# AJMG_2550XD_Silver_Jubilee_-_wersja_pryw.net
KiCad netlist of a schematic drawn in Altium Designer
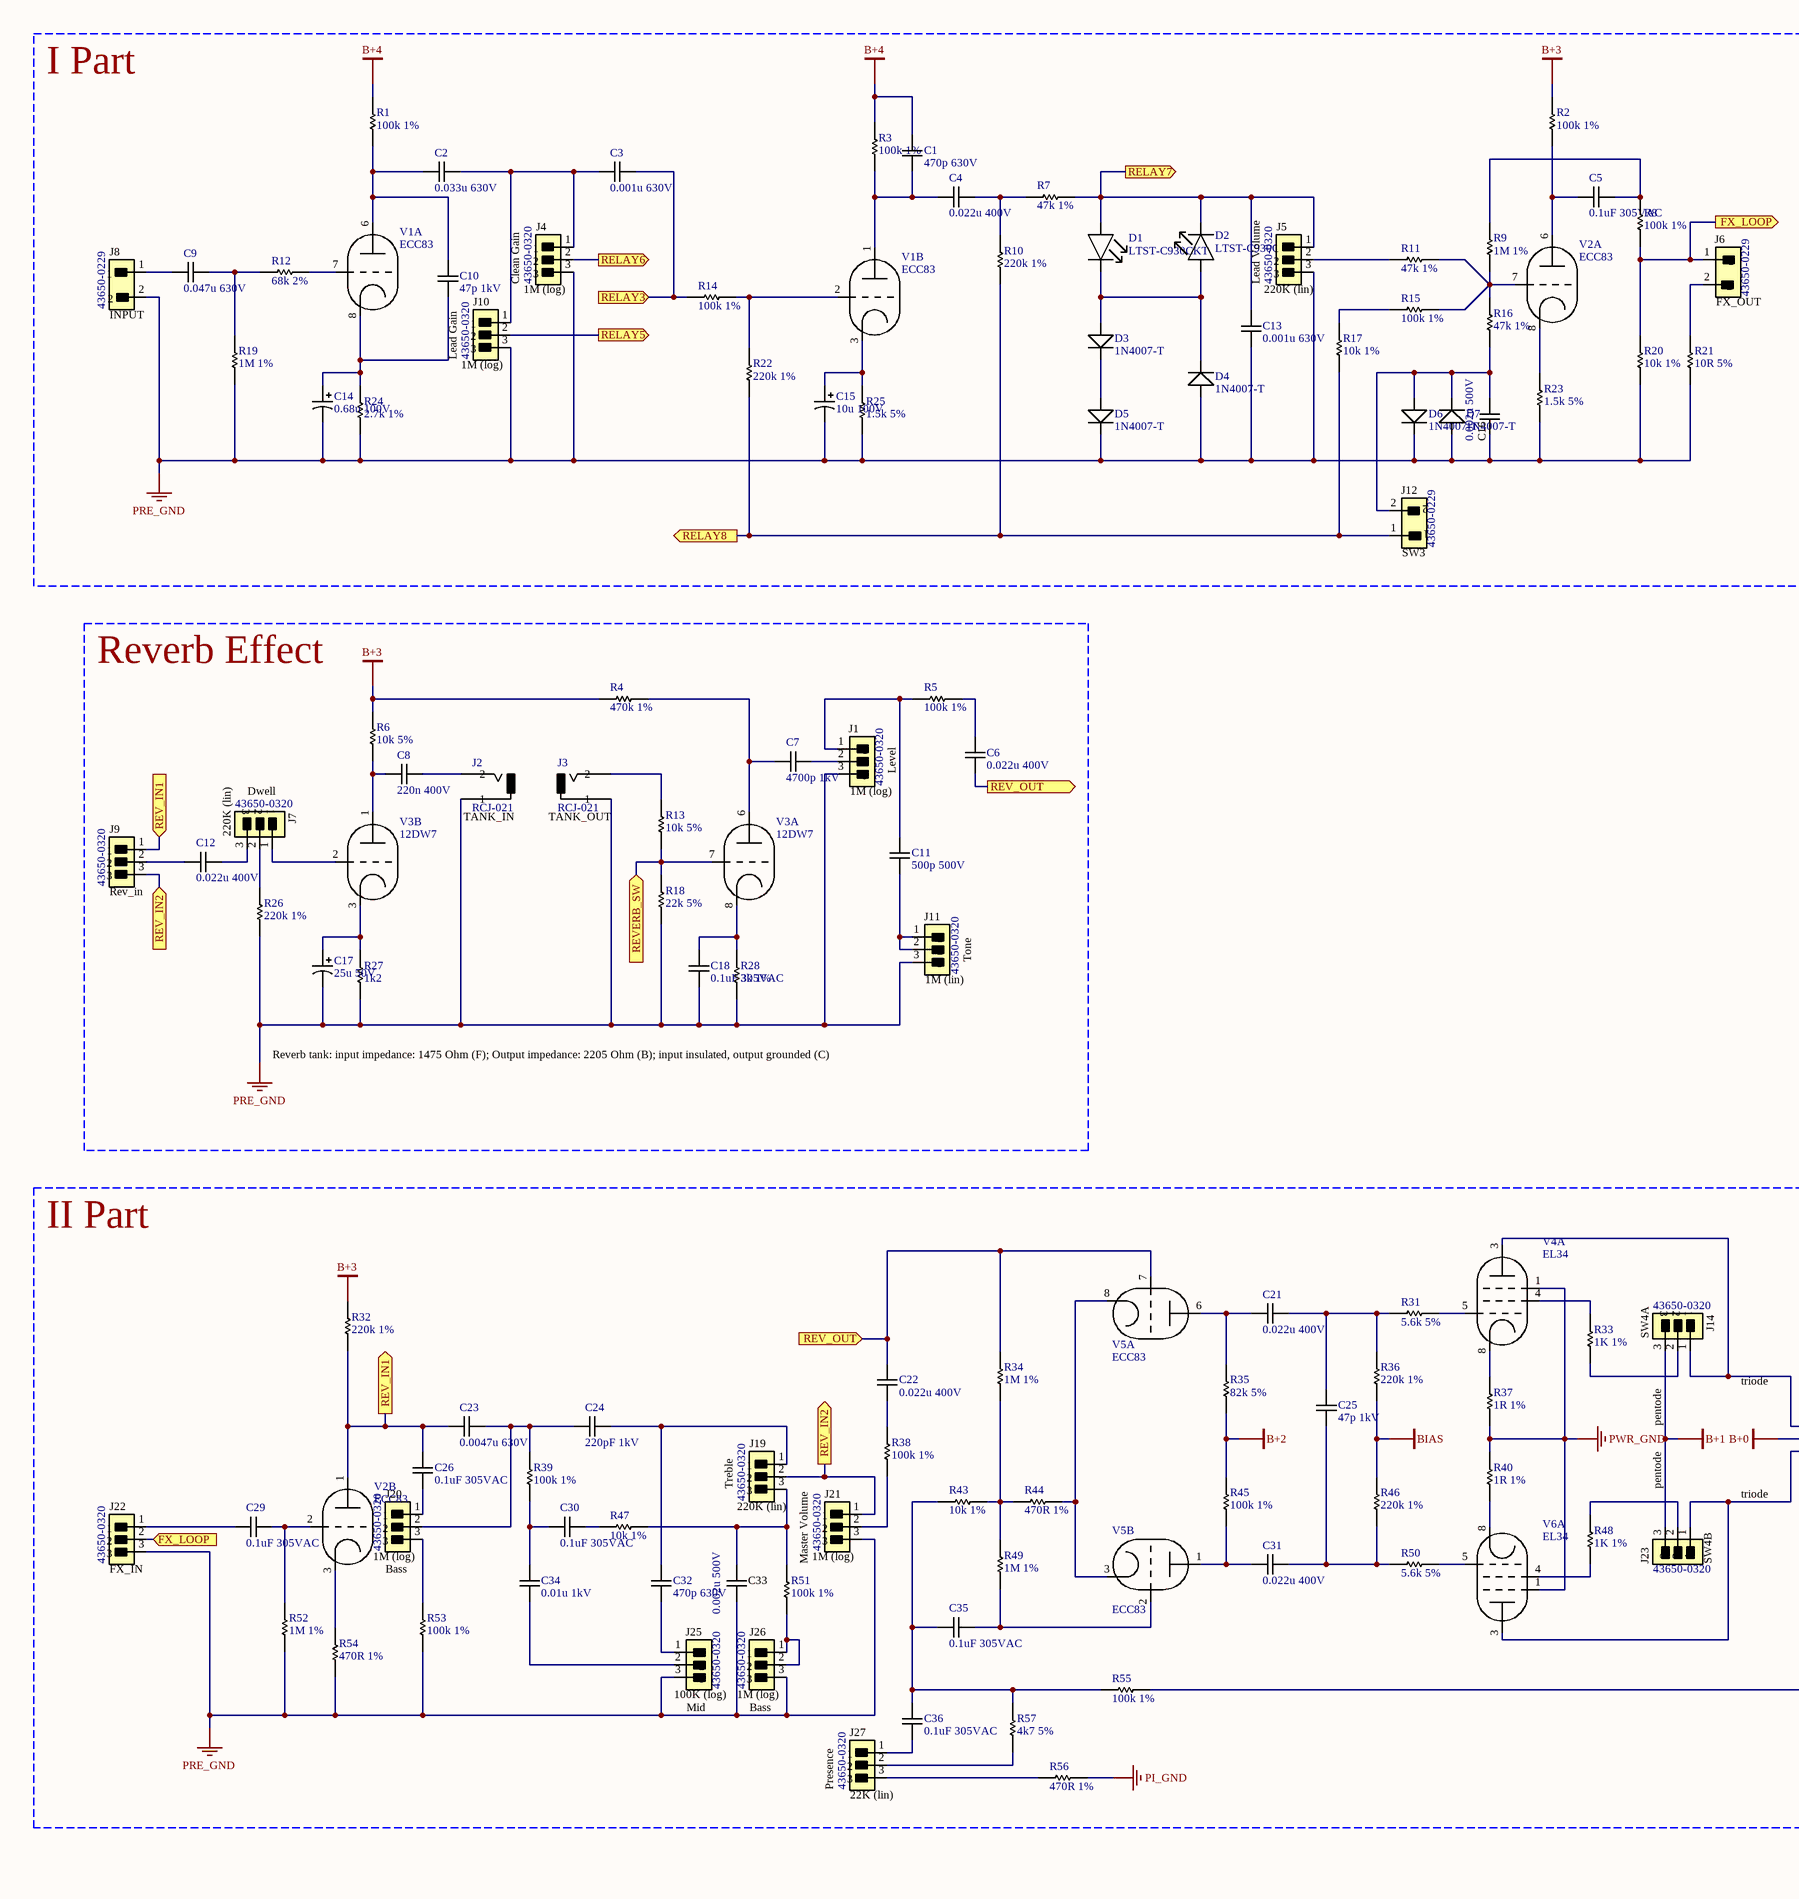
[diagram p0: AJMG 2550XD Silver Jubilee - wersja prywatna.SchDoc, left]
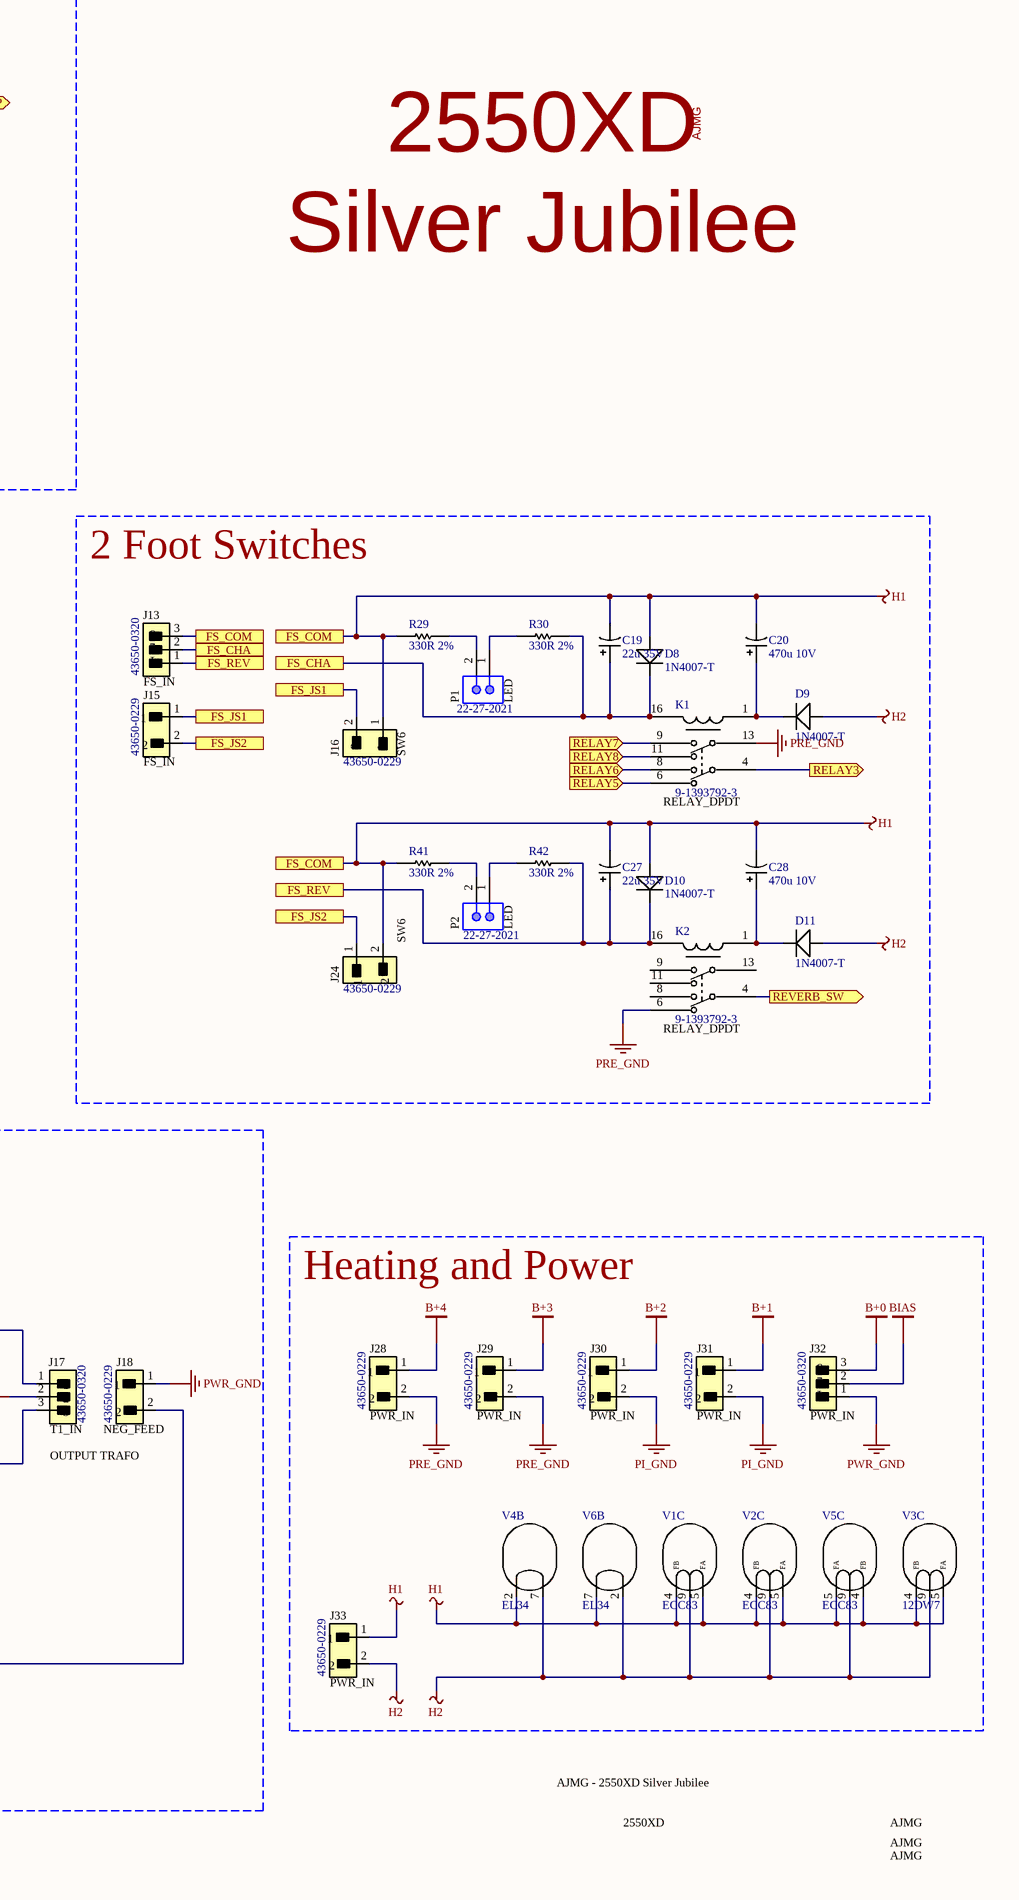
[diagram p1: AJMG 2550XD Silver Jubilee - wersja prywatna.SchDoc, right]

(export (version "E")
  (design (tool "Eeschema 10.0.6"))
  (components
    (comp (ref "C1")
      (value "470p 630V")
      (footprint "C_THT_5mm_7.2x4.5_NOT_POLARISED")
      (description "CAP FILM THT 7.2x4.5 470pF 630V 10%")
      (fields
        (field (name "MANUFACTURER") "WIMA")
        (field (name "MANUFACTURER PART NUMBER") "FKP2J004701D00KSSD")
      )
      (libsource (lib "Schematic Library - AJMG 2550XD Silver Jubilee") (part "FKP2J004701D00KSSD"))
    )
    (comp (ref "C2")
      (value "0.033u 630V")
      (footprint "C_THT_7.5mm_10.5x5_NOT_POLARISED")
      (description "CAP FILM THT 10.5x5 0.033uF 630V 5%")
      (fields
        (field (name "MANUFACTURER") "Wurth Elektronik")
        (field (name "MANUFACTURER PART NUMBER") "890303322005CS")
      )
      (libsource (lib "Schematic Library - AJMG 2550XD Silver Jubilee") (part "890303322005CS"))
    )
    (comp (ref "C3")
      (value "0.001u 630V")
      (footprint "C_THT_5mm_7.2x4.5_NOT_POLARISED")
      (description "CAP FILM THT 7.2x4.5 0.001uF 630V 10%")
      (fields
        (field (name "MANUFACTURER") "WIMA")
        (field (name "MANUFACTURER PART NUMBER") "FKP2J011001D00KI00")
      )
      (libsource (lib "Schematic Library - AJMG 2550XD Silver Jubilee") (part "FKP2J011001D00KI00"))
    )
    (comp (ref "C4")
      (value "0.022u 400V")
      (footprint "C_THT_10mm_13x5_NOT_POLARISED")
      (description "CAP FILM THT 13x4 0.022uF 400V 10%")
      (fields
        (field (name "MANUFACTURER") "WIMA")
        (field (name "MANUFACTURER PART NUMBER") "MKP4G022203C00KSSD")
      )
      (libsource (lib "Schematic Library - AJMG 2550XD Silver Jubilee") (part "MKP4G022203C00KSSD"))
    )
    (comp (ref "C5")
      (value "0.1uF 305VAC")
      (footprint "C_THT_10mm_13x5.5_NOT_POLARISED")
      (description "CAP FILM THT 13x6 0.1uF 305V(AC) 10%")
      (fields
        (field (name "MANUFACTURER") "Cornell Dubilier")
        (field (name "MANUFACTURER PART NUMBER") "MPX104K305D")
      )
      (libsource (lib "Schematic Library - AJMG 2550XD Silver Jubilee") (part "MPX104K305D"))
    )
    (comp (ref "C6")
      (value "0.022u 400V")
      (footprint "C_THT_10mm_13x5_NOT_POLARISED")
      (description "CAP FILM THT 13x4 0.022uF 400V 10%")
      (fields
        (field (name "MANUFACTURER") "WIMA")
        (field (name "MANUFACTURER PART NUMBER") "MKP4G022203C00KSSD")
      )
      (libsource (lib "Schematic Library - AJMG 2550XD Silver Jubilee") (part "MKP4G022203C00KSSD"))
    )
    (comp (ref "C7")
      (value "4700p 1kV")
      (footprint "C_THT_10mm_13x5_NOT_POLARISED")
      (description "CAP FILM THT 13x4 4700pF 1kV 10%")
      (fields
        (field (name "MANUFACTURER") "WIMA")
        (field (name "MANUFACTURER PART NUMBER") "MKP10-4700/1KV/10P10")
      )
      (libsource (lib "Schematic Library - AJMG 2550XD Silver Jubilee") (part "MKP10-4700/1KV/10P10"))
    )
    (comp (ref "C8")
      (value "220n 400V")
      (footprint "C_THT_15mm_18x5_NOT_POLARISED")
      (description "CAP FILM THT 18x5 220nF 400V 10%")
      (fields
        (field (name "MANUFACTURER") "Wurth Elektronik")
        (field (name "MANUFACTURER PART NUMBER") "890283425002CS")
      )
      (libsource (lib "Schematic Library - AJMG 2550XD Silver Jubilee") (part "890283425002CS"))
    )
    (comp (ref "C9")
      (value "0.047u 630V")
      (footprint "C_THT_7.5mm_10.5x6_NOT_POLARISED")
      (description "CAP FILM THT 10.5x6 0.047uF 630V 10%")
      (fields
        (field (name "MANUFACTURER") "Wurth Elektronik")
        (field (name "MANUFACTURER PART NUMBER") "890303422005CS")
      )
      (libsource (lib "Schematic Library - AJMG 2550XD Silver Jubilee") (part "890303422005CS"))
    )
    (comp (ref "C10")
      (value "47p 1kV")
      (footprint "C_THT_15mm_16.3x4.8_NOT_POLARISED")
      (description "CAP MICA THT 16.3x4.8 47pF 1kV 5%")
      (fields
        (field (name "MANUFACTURER") "Cornell Dubilier")
        (field (name "MANUFACTURER PART NUMBER") "CDV19EF470JO3F")
      )
      (libsource (lib "Schematic Library - AJMG 2550XD Silver Jubilee") (part "CDV19EF470JO3F"))
    )
    (comp (ref "C11")
      (value "500p 500V")
      (footprint "C_THT_9mm_16.25x5_NOT_POLARISED")
      (description "CAP MICA THT 16.3x5 500pF 500V 5%")
      (fields
        (field (name "MANUFACTURER") "Cornell Dubilier")
        (field (name "MANUFACTURER PART NUMBER") "CD19FD501JO3F")
      )
      (libsource (lib "Schematic Library - AJMG 2550XD Silver Jubilee") (part "CD19FD501JO3F"))
    )
    (comp (ref "C12")
      (value "0.022u 400V")
      (footprint "C_THT_10mm_13x5_NOT_POLARISED")
      (description "CAP FILM THT 13x4 0.022uF 400V 10%")
      (fields
        (field (name "MANUFACTURER") "WIMA")
        (field (name "MANUFACTURER PART NUMBER") "MKP4G022203C00KSSD")
      )
      (libsource (lib "Schematic Library - AJMG 2550XD Silver Jubilee") (part "MKP4G022203C00KSSD"))
    )
    (comp (ref "C13")
      (value "0.001u 630V")
      (footprint "C_THT_5mm_7.2x4.5_NOT_POLARISED")
      (description "CAP FILM THT 7.2x4.5 0.001uF 630V 10%")
      (fields
        (field (name "MANUFACTURER") "WIMA")
        (field (name "MANUFACTURER PART NUMBER") "FKP2J011001D00KI00")
      )
      (libsource (lib "Schematic Library - AJMG 2550XD Silver Jubilee") (part "FKP2J011001D00KI00"))
    )
    (comp (ref "C14")
      (value "0.68u 100V")
      (footprint "C_THT_2mm_D5H11_POLARISED")
      (description "CAP ALUM THT D5xH11 0.68uF 100V 20%")
      (fields
        (field (name "MANUFACTURER") "Nichicon")
        (field (name "MANUFACTURER PART NUMBER") "UKL2AR68KDD1TA")
      )
      (libsource (lib "Schematic Library - AJMG 2550XD Silver Jubilee") (part "UKL2AR68KDD1TA"))
    )
    (comp (ref "C15")
      (value "10u 100V")
      (footprint "C_THT_2mm_D5H11_POLARISED")
      (description "CAP ALUM THT D5xH11 10uF 100V 20%")
      (fields
        (field (name "MANUFACTURER") "Rubycon")
        (field (name "MANUFACTURER PART NUMBER") "100PK10MEFC5X11")
      )
      (libsource (lib "Schematic Library - AJMG 2550XD Silver Jubilee") (part "100PK10MEFC5X11"))
    )
    (comp (ref "C16")
      (value "0.002u 500V")
      (footprint "C_THT_8mm_16x5_NOT_POLARISED")
      (description "CAP MICA THT AxB 0.002uF 500V 5%")
      (libsource (lib "Schematic Library - AJMG 2550XD Silver Jubilee") (part "TAD SILVER MICA CAPS"))
    )
    (comp (ref "C17")
      (value "25u 50V")
      (footprint "C_THT_22.5mm_D6.35xH17.45_AXIAL_POLARISED")
      (description "CAP ALUM THT AXIAL D6.35xH17.45 25uF 50V 20%")
      (fields (field (name "MANUFACTURER") "Vishay") (field (name "MANUFACTURER PART NUMBER") "TVA1306"))
      (libsource (lib "Schematic Library - AJMG 2550XD Silver Jubilee") (part "TVA1306"))
    )
    (comp (ref "C18")
      (value "0.1uF 305VAC")
      (footprint "C_THT_10mm_13x5.5_NOT_POLARISED")
      (description "CAP FILM THT 13x6 0.1uF 305V(AC) 10%")
      (fields
        (field (name "MANUFACTURER") "Cornell Dubilier")
        (field (name "MANUFACTURER PART NUMBER") "MPX104K305D")
      )
      (libsource (lib "Schematic Library - AJMG 2550XD Silver Jubilee") (part "MPX104K305D"))
    )
    (comp (ref "C19")
      (value "22u 35V")
      (footprint "C_THT_2mm_D5H11_POLARISED")
      (description "CAP ALUM THT D5xH11 22uF 35V 20%")
      (fields
        (field (name "MANUFACTURER PART NUMBER") "860010572003")
        (field (name "MANUFACTURER") "Wurth Elektronik")
      )
      (libsource (lib "Schematic Library - AJMG 2550XD Silver Jubilee") (part "860010572003"))
    )
    (comp (ref "C20")
      (value "470u 10V")
      (footprint "C_THT_2.5mm_D6.3H11_POLARISED")
      (description "CAP ALUM THT D6.3xH11 470uF 10V 20%")
      (fields
        (field (name "MANUFACTURER PART NUMBER") "860010273011")
        (field (name "MANUFACTURER") "Wurth Elektronik")
      )
      (libsource (lib "Schematic Library - AJMG 2550XD Silver Jubilee") (part "860010273011"))
    )
    (comp (ref "C21")
      (value "0.022u 400V")
      (footprint "C_THT_10mm_13x5_NOT_POLARISED")
      (description "CAP FILM THT 13x4 0.022uF 400V 10%")
      (fields
        (field (name "MANUFACTURER") "WIMA")
        (field (name "MANUFACTURER PART NUMBER") "MKP4G022203C00KSSD")
      )
      (libsource (lib "Schematic Library - AJMG 2550XD Silver Jubilee") (part "MKP4G022203C00KSSD"))
    )
    (comp (ref "C22")
      (value "0.022u 400V")
      (footprint "C_THT_10mm_13x5_NOT_POLARISED")
      (description "CAP FILM THT 13x4 0.022uF 400V 10%")
      (fields
        (field (name "MANUFACTURER") "WIMA")
        (field (name "MANUFACTURER PART NUMBER") "MKP4G022203C00KSSD")
      )
      (libsource (lib "Schematic Library - AJMG 2550XD Silver Jubilee") (part "MKP4G022203C00KSSD"))
    )
    (comp (ref "C23")
      (value "0.0047u 630V")
      (footprint "C_THT_5mm_7.2x6.5_NOT_POLARISED")
      (description "CAP FILM THT 7.2x6.5 0.0047uF 630V 5%")
      (fields
        (field (name "MANUFACTURER") "WIMA")
        (field (name "MANUFACTURER PART NUMBER") "FKP2J014701I00JSSD")
      )
      (libsource (lib "Schematic Library - AJMG 2550XD Silver Jubilee") (part "FKP2J014701I00JSSD"))
    )
    (comp (ref "C24")
      (value "220pF 1kV")
      (footprint "C_THT_7.5mm_10.9x3.8_NOT_POLARISED")
      (description "CAP MICA THT 10.9x3.8 220pF 1kV 5%")
      (fields
        (field (name "MANUFACTURER") "Cornell Dubilier")
        (field (name "MANUFACTURER PART NUMBER") "CDV16FF221JO3F")
      )
      (libsource (lib "Schematic Library - AJMG 2550XD Silver Jubilee") (part "CDV16FF221JO3F"))
    )
    (comp (ref "C25")
      (value "47p 1kV")
      (footprint "C_THT_15mm_16.3x4.8_NOT_POLARISED")
      (description "CAP MICA THT 16.3x4.8 47pF 1kV 5%")
      (fields
        (field (name "MANUFACTURER") "Cornell Dubilier")
        (field (name "MANUFACTURER PART NUMBER") "CDV19EF470JO3F")
      )
      (libsource (lib "Schematic Library - AJMG 2550XD Silver Jubilee") (part "CDV19EF470JO3F"))
    )
    (comp (ref "C26")
      (value "0.1uF 305VAC")
      (footprint "C_THT_10mm_13x5.5_NOT_POLARISED")
      (description "CAP FILM THT 13x6 0.1uF 305V(AC) 10%")
      (fields
        (field (name "MANUFACTURER") "Cornell Dubilier")
        (field (name "MANUFACTURER PART NUMBER") "MPX104K305D")
      )
      (libsource (lib "Schematic Library - AJMG 2550XD Silver Jubilee") (part "MPX104K305D"))
    )
    (comp (ref "C27")
      (value "22u 35V")
      (footprint "C_THT_2mm_D5H11_POLARISED")
      (description "CAP ALUM THT D5xH11 22uF 35V 20%")
      (fields
        (field (name "MANUFACTURER PART NUMBER") "860010572003")
        (field (name "MANUFACTURER") "Wurth Elektronik")
      )
      (libsource (lib "Schematic Library - AJMG 2550XD Silver Jubilee") (part "860010572003"))
    )
    (comp (ref "C28")
      (value "470u 10V")
      (footprint "C_THT_2.5mm_D6.3H11_POLARISED")
      (description "CAP ALUM THT D6.3xH11 470uF 10V 20%")
      (fields
        (field (name "MANUFACTURER PART NUMBER") "860010273011")
        (field (name "MANUFACTURER") "Wurth Elektronik")
      )
      (libsource (lib "Schematic Library - AJMG 2550XD Silver Jubilee") (part "860010273011"))
    )
    (comp (ref "C29")
      (value "0.1uF 305VAC")
      (footprint "C_THT_10mm_13x5.5_NOT_POLARISED")
      (description "CAP FILM THT 13x6 0.1uF 305V(AC) 10%")
      (fields
        (field (name "MANUFACTURER") "Cornell Dubilier")
        (field (name "MANUFACTURER PART NUMBER") "MPX104K305D")
      )
      (libsource (lib "Schematic Library - AJMG 2550XD Silver Jubilee") (part "MPX104K305D"))
    )
    (comp (ref "C30")
      (value "0.1uF 305VAC")
      (footprint "C_THT_10mm_13x5.5_NOT_POLARISED")
      (description "CAP FILM THT 13x6 0.1uF 305V(AC) 10%")
      (fields
        (field (name "MANUFACTURER") "Cornell Dubilier")
        (field (name "MANUFACTURER PART NUMBER") "MPX104K305D")
      )
      (libsource (lib "Schematic Library - AJMG 2550XD Silver Jubilee") (part "MPX104K305D"))
    )
    (comp (ref "C31")
      (value "0.022u 400V")
      (footprint "C_THT_10mm_13x5_NOT_POLARISED")
      (description "CAP FILM THT 13x4 0.022uF 400V 10%")
      (fields
        (field (name "MANUFACTURER") "WIMA")
        (field (name "MANUFACTURER PART NUMBER") "MKP4G022203C00KSSD")
      )
      (libsource (lib "Schematic Library - AJMG 2550XD Silver Jubilee") (part "MKP4G022203C00KSSD"))
    )
    (comp (ref "C32")
      (value "470p 630V")
      (footprint "C_THT_5mm_7.2x4.5_NOT_POLARISED")
      (description "CAP FILM THT 7.2x4.5 470pF 630V 10%")
      (fields
        (field (name "MANUFACTURER") "WIMA")
        (field (name "MANUFACTURER PART NUMBER") "FKP2J004701D00KSSD")
      )
      (libsource (lib "Schematic Library - AJMG 2550XD Silver Jubilee") (part "FKP2J004701D00KSSD"))
    )
    (comp (ref "C33")
      (value "0.002u 500V")
      (footprint "C_THT_8mm_16x5_NOT_POLARISED")
      (description "CAP MICA THT AxB 0.002uF 500V 5%")
      (libsource (lib "Schematic Library - AJMG 2550XD Silver Jubilee") (part "TAD SILVER MICA CAPS"))
    )
    (comp (ref "C34")
      (value "0.01u 1kV")
      (footprint "C_THT_7.5mm_10.5x6_NOT_POLARISED")
      (description "CAP FILM THT 10.5x6 0.01uF 1kV 10%")
      (fields
        (field (name "MANUFACTURER") "Wurth Elektronik")
        (field (name "MANUFACTURER PART NUMBER") "890493422002CS")
      )
      (libsource (lib "Schematic Library - AJMG 2550XD Silver Jubilee") (part "890493422002CS"))
    )
    (comp (ref "C35")
      (value "0.1uF 305VAC")
      (footprint "C_THT_10mm_13x5.5_NOT_POLARISED")
      (description "CAP FILM THT 13x6 0.1uF 305V(AC) 10%")
      (fields
        (field (name "MANUFACTURER") "Cornell Dubilier")
        (field (name "MANUFACTURER PART NUMBER") "MPX104K305D")
      )
      (libsource (lib "Schematic Library - AJMG 2550XD Silver Jubilee") (part "MPX104K305D"))
    )
    (comp (ref "C36")
      (value "0.1uF 305VAC")
      (footprint "C_THT_10mm_13x5.5_NOT_POLARISED")
      (description "CAP FILM THT 13x6 0.1uF 305V(AC) 10%")
      (fields
        (field (name "MANUFACTURER") "Cornell Dubilier")
        (field (name "MANUFACTURER PART NUMBER") "MPX104K305D")
      )
      (libsource (lib "Schematic Library - AJMG 2550XD Silver Jubilee") (part "MPX104K305D"))
    )
    (comp (ref "D1")
      (value "LTST-C930CKT")
      (footprint "D_LTST-C930CKT")
      (description "DIODE LED SMD")
      (fields
        (field (name "OCTOPART") "https://octopart.com/ltst-c930kskt-lite-on-549925")
        (field (name "MANUFACTURER PART NUMBER") "LTST-C930KSKT")
      )
      (libsource (lib "Schematic Library - AJMG 2550XD Silver Jubilee") (part "LTST-C930CKT"))
    )
    (comp (ref "D2")
      (value "LTST-C930CKT")
      (footprint "D_LTST-C930CKT")
      (description "DIODE LED SMD")
      (fields
        (field (name "OCTOPART") "https://octopart.com/ltst-c930kskt-lite-on-549925")
        (field (name "MANUFACTURER PART NUMBER") "LTST-C930KSKT")
      )
      (libsource (lib "Schematic Library - AJMG 2550XD Silver Jubilee") (part "LTST-C930CKT"))
    )
    (comp (ref "D3")
      (value "1N4007-T")
      (footprint "D_1N4007-T")
      (description "DIODE\r\n1.0 A Rectifier, 8 pF, 1000 V, -65 to 150 degC, 2-Pin DO-41 Plastic, RoHS, Tape and Reel")
      (fields (field (name "MANUFACTURER") "Diodes Inc"))
      (libsource (lib "Schematic Library - AJMG 2550XD Silver Jubilee") (part "1N4007-T"))
    )
    (comp (ref "D4")
      (value "1N4007-T")
      (footprint "D_1N4007-T")
      (description "DIODE\r\n1.0 A Rectifier, 8 pF, 1000 V, -65 to 150 degC, 2-Pin DO-41 Plastic, RoHS, Tape and Reel")
      (fields (field (name "MANUFACTURER") "Diodes Inc"))
      (libsource (lib "Schematic Library - AJMG 2550XD Silver Jubilee") (part "1N4007-T"))
    )
    (comp (ref "D5")
      (value "1N4007-T")
      (footprint "D_1N4007-T")
      (description "DIODE\r\n1.0 A Rectifier, 8 pF, 1000 V, -65 to 150 degC, 2-Pin DO-41 Plastic, RoHS, Tape and Reel")
      (fields (field (name "MANUFACTURER") "Diodes Inc"))
      (libsource (lib "Schematic Library - AJMG 2550XD Silver Jubilee") (part "1N4007-T"))
    )
    (comp (ref "D6")
      (value "1N4007-T")
      (footprint "D_1N4007-T")
      (description "DIODE\r\n1.0 A Rectifier, 8 pF, 1000 V, -65 to 150 degC, 2-Pin DO-41 Plastic, RoHS, Tape and Reel")
      (fields (field (name "MANUFACTURER") "Diodes Inc"))
      (libsource (lib "Schematic Library - AJMG 2550XD Silver Jubilee") (part "1N4007-T"))
    )
    (comp (ref "D7")
      (value "1N4007-T")
      (footprint "D_1N4007-T")
      (description "DIODE\r\n1.0 A Rectifier, 8 pF, 1000 V, -65 to 150 degC, 2-Pin DO-41 Plastic, RoHS, Tape and Reel")
      (fields (field (name "MANUFACTURER") "Diodes Inc"))
      (libsource (lib "Schematic Library - AJMG 2550XD Silver Jubilee") (part "1N4007-T"))
    )
    (comp (ref "D8")
      (value "1N4007-T")
      (footprint "D_1N4007-T")
      (description "DIODE\r\n1.0 A Rectifier, 8 pF, 1000 V, -65 to 150 degC, 2-Pin DO-41 Plastic, RoHS, Tape and Reel")
      (fields (field (name "MANUFACTURER") "Diodes Inc"))
      (libsource (lib "Schematic Library - AJMG 2550XD Silver Jubilee") (part "1N4007-T"))
    )
    (comp (ref "D9")
      (value "1N4007-T")
      (footprint "D_1N4007-T")
      (description "DIODE\r\n1.0 A Rectifier, 8 pF, 1000 V, -65 to 150 degC, 2-Pin DO-41 Plastic, RoHS, Tape and Reel")
      (fields (field (name "MANUFACTURER") "Diodes Inc"))
      (libsource (lib "Schematic Library - AJMG 2550XD Silver Jubilee") (part "1N4007-T"))
    )
    (comp (ref "D10")
      (value "1N4007-T")
      (footprint "D_1N4007-T")
      (description "DIODE\r\n1.0 A Rectifier, 8 pF, 1000 V, -65 to 150 degC, 2-Pin DO-41 Plastic, RoHS, Tape and Reel")
      (fields (field (name "MANUFACTURER") "Diodes Inc"))
      (libsource (lib "Schematic Library - AJMG 2550XD Silver Jubilee") (part "1N4007-T"))
    )
    (comp (ref "D11")
      (value "1N4007-T")
      (footprint "D_1N4007-T")
      (description "DIODE\r\n1.0 A Rectifier, 8 pF, 1000 V, -65 to 150 degC, 2-Pin DO-41 Plastic, RoHS, Tape and Reel")
      (fields (field (name "MANUFACTURER") "Diodes Inc"))
      (libsource (lib "Schematic Library - AJMG 2550XD Silver Jubilee") (part "1N4007-T"))
    )
    (comp (ref "J1")
      (value "43650-0320")
      (footprint "CONN HEADER VERT 3POS 3MM")
      (description "CONN HEADER VERT 3POS 3MM")
      (fields
        (field (name "MANUFACTURER") "Molex")
        (field (name "OCTOPART") "https://octopart.com/43650-0320-molex-7670312")
      )
      (libsource (lib "Schematic Library - AJMG 2550XD Silver Jubilee") (part "CMP-04776-000004-1"))
    )
    (comp (ref "J2")
      (value "RCJ-021")
      (footprint "CONN_CUI_RCJ-021")
      (description "CONN RCA JACK MONO 3.2MM PCB")
      (fields (field (name "MANUFACTURER") "CUI"))
      (libsource (lib "Schematic Library - AJMG 2550XD Silver Jubilee") (part "RCJ-021"))
    )
    (comp (ref "J3")
      (value "RCJ-021")
      (footprint "CONN_CUI_RCJ-021")
      (description "CONN RCA JACK MONO 3.2MM PCB")
      (fields (field (name "MANUFACTURER") "CUI"))
      (libsource (lib "") (part "RCJ-021_1"))
    )
    (comp (ref "J4")
      (value "43650-0320")
      (footprint "CONN HEADER VERT 3POS 3MM")
      (description "CONN HEADER VERT 3POS 3MM")
      (fields
        (field (name "MANUFACTURER") "Molex")
        (field (name "OCTOPART") "https://octopart.com/43650-0320-molex-7670312")
      )
      (libsource (lib "") (part "CMP-04776-000004-1_2"))
    )
    (comp (ref "J5")
      (value "43650-0320")
      (footprint "CONN HEADER VERT 3POS 3MM")
      (description "CONN HEADER VERT 3POS 3MM")
      (fields
        (field (name "MANUFACTURER") "Molex")
        (field (name "OCTOPART") "https://octopart.com/43650-0320-molex-7670312")
      )
      (libsource (lib "") (part "CMP-04776-000004-1_2"))
    )
    (comp (ref "J6")
      (value "43650-0229")
      (footprint "CONN HEADER VERT 2POS 3MM")
      (description "CONN HEADER VERT 2POS 3MM")
      (fields
        (field (name "OCTOPART") "https://octopart.com/43650-0229-molex-7652326")
        (field (name "MANUFACTURER") "Molex")
      )
      (libsource (lib "") (part "CMP-04776-000041-1_1"))
    )
    (comp (ref "J7")
      (value "43650-0320")
      (footprint "CONN HEADER VERT 3POS 3MM")
      (description "CONN HEADER VERT 3POS 3MM")
      (fields
        (field (name "MANUFACTURER") "Molex")
        (field (name "OCTOPART") "https://octopart.com/43650-0320-molex-7670312")
      )
      (libsource (lib "Schematic Library - AJMG 2550XD Silver Jubilee") (part "CMP-04776-000004-1"))
    )
    (comp (ref "J8")
      (value "43650-0229")
      (footprint "CONN HEADER VERT 2POS 3MM")
      (description "CONN HEADER VERT 2POS 3MM")
      (fields
        (field (name "OCTOPART") "https://octopart.com/43650-0229-molex-7652326")
        (field (name "MANUFACTURER") "Molex")
      )
      (libsource (lib "Schematic Library - AJMG 2550XD Silver Jubilee") (part "CMP-04776-000041-1"))
    )
    (comp (ref "J9")
      (value "43650-0320")
      (footprint "CONN HEADER VERT 3POS 3MM")
      (description "CONN HEADER VERT 3POS 3MM")
      (fields
        (field (name "MANUFACTURER") "Molex")
        (field (name "OCTOPART") "https://octopart.com/43650-0320-molex-7670312")
      )
      (libsource (lib "") (part "CMP-04776-000004-1_2"))
    )
    (comp (ref "J10")
      (value "43650-0320")
      (footprint "CONN HEADER VERT 3POS 3MM")
      (description "CONN HEADER VERT 3POS 3MM")
      (fields
        (field (name "MANUFACTURER") "Molex")
        (field (name "OCTOPART") "https://octopart.com/43650-0320-molex-7670312")
      )
      (libsource (lib "") (part "CMP-04776-000004-1_2"))
    )
    (comp (ref "J11")
      (value "43650-0320")
      (footprint "CONN HEADER VERT 3POS 3MM")
      (description "CONN HEADER VERT 3POS 3MM")
      (fields
        (field (name "MANUFACTURER") "Molex")
        (field (name "OCTOPART") "https://octopart.com/43650-0320-molex-7670312")
      )
      (libsource (lib "Schematic Library - AJMG 2550XD Silver Jubilee") (part "CMP-04776-000004-1"))
    )
    (comp (ref "J12")
      (value "43650-0229")
      (footprint "CONN HEADER VERT 2POS 3MM")
      (description "CONN HEADER VERT 2POS 3MM")
      (fields
        (field (name "OCTOPART") "https://octopart.com/43650-0229-molex-7652326")
        (field (name "MANUFACTURER") "Molex")
      )
      (libsource (lib "") (part "CMP-04776-000041-1_3"))
    )
    (comp (ref "J13")
      (value "43650-0320")
      (footprint "CONN HEADER VERT 3POS 3MM")
      (description "CONN HEADER VERT 3POS 3MM")
      (fields
        (field (name "MANUFACTURER") "Molex")
        (field (name "OCTOPART") "https://octopart.com/43650-0320-molex-7670312")
      )
      (libsource (lib "") (part "CMP-04776-000004-1_1"))
    )
    (comp (ref "J14")
      (value "43650-0320")
      (footprint "CONN HEADER VERT 3POS 3MM")
      (description "CONN HEADER VERT 3POS 3MM")
      (fields
        (field (name "MANUFACTURER") "Molex")
        (field (name "OCTOPART") "https://octopart.com/43650-0320-molex-7670312")
      )
      (libsource (lib "Schematic Library - AJMG 2550XD Silver Jubilee") (part "CMP-04776-000004-1"))
    )
    (comp (ref "J15")
      (value "43650-0229")
      (footprint "CONN HEADER VERT 2POS 3MM")
      (description "CONN HEADER VERT 2POS 3MM")
      (fields
        (field (name "OCTOPART") "https://octopart.com/43650-0229-molex-7652326")
        (field (name "MANUFACTURER") "Molex")
      )
      (libsource (lib "Schematic Library - AJMG 2550XD Silver Jubilee") (part "CMP-04776-000041-1"))
    )
    (comp (ref "J16")
      (value "43650-0229")
      (footprint "CONN HEADER VERT 2POS 3MM")
      (description "CONN HEADER VERT 2POS 3MM")
      (fields
        (field (name "OCTOPART") "https://octopart.com/43650-0229-molex-7652326")
        (field (name "MANUFACTURER") "Molex")
      )
      (libsource (lib "Schematic Library - AJMG 2550XD Silver Jubilee") (part "CMP-04776-000041-1"))
    )
    (comp (ref "J17")
      (value "43650-0320")
      (footprint "CONN HEADER VERT 3POS 3MM")
      (description "CONN HEADER VERT 3POS 3MM")
      (fields
        (field (name "MANUFACTURER") "Molex")
        (field (name "OCTOPART") "https://octopart.com/43650-0320-molex-7670312")
      )
      (libsource (lib "Schematic Library - AJMG 2550XD Silver Jubilee") (part "CMP-04776-000004-1"))
    )
    (comp (ref "J18")
      (value "43650-0229")
      (footprint "CONN HEADER VERT 2POS 3MM")
      (description "CONN HEADER VERT 2POS 3MM")
      (fields
        (field (name "OCTOPART") "https://octopart.com/43650-0229-molex-7652326")
        (field (name "MANUFACTURER") "Molex")
      )
      (libsource (lib "Schematic Library - AJMG 2550XD Silver Jubilee") (part "CMP-04776-000041-1"))
    )
    (comp (ref "J19")
      (value "43650-0320")
      (footprint "CONN HEADER VERT 3POS 3MM")
      (description "CONN HEADER VERT 3POS 3MM")
      (fields
        (field (name "MANUFACTURER") "Molex")
        (field (name "OCTOPART") "https://octopart.com/43650-0320-molex-7670312")
      )
      (libsource (lib "") (part "CMP-04776-000004-1_2"))
    )
    (comp (ref "J20")
      (value "43650-0320")
      (footprint "CONN HEADER VERT 3POS 3MM")
      (description "CONN HEADER VERT 3POS 3MM")
      (fields
        (field (name "MANUFACTURER") "Molex")
        (field (name "OCTOPART") "https://octopart.com/43650-0320-molex-7670312")
      )
      (libsource (lib "") (part "CMP-04776-000004-1_2"))
    )
    (comp (ref "J21")
      (value "43650-0320")
      (footprint "CONN HEADER VERT 3POS 3MM")
      (description "CONN HEADER VERT 3POS 3MM")
      (fields
        (field (name "MANUFACTURER") "Molex")
        (field (name "OCTOPART") "https://octopart.com/43650-0320-molex-7670312")
      )
      (libsource (lib "") (part "CMP-04776-000004-1_2"))
    )
    (comp (ref "J22")
      (value "43650-0320")
      (footprint "CONN HEADER VERT 3POS 3MM")
      (description "CONN HEADER VERT 3POS 3MM")
      (fields
        (field (name "MANUFACTURER") "Molex")
        (field (name "OCTOPART") "https://octopart.com/43650-0320-molex-7670312")
      )
      (libsource (lib "") (part "CMP-04776-000004-1_2"))
    )
    (comp (ref "J23")
      (value "43650-0320")
      (footprint "CONN HEADER VERT 3POS 3MM")
      (description "CONN HEADER VERT 3POS 3MM")
      (fields
        (field (name "MANUFACTURER") "Molex")
        (field (name "OCTOPART") "https://octopart.com/43650-0320-molex-7670312")
      )
      (libsource (lib "") (part "CMP-04776-000004-1_2"))
    )
    (comp (ref "J24")
      (value "43650-0229")
      (footprint "CONN HEADER VERT 2POS 3MM")
      (description "CONN HEADER VERT 2POS 3MM")
      (fields
        (field (name "OCTOPART") "https://octopart.com/43650-0229-molex-7652326")
        (field (name "MANUFACTURER") "Molex")
      )
      (libsource (lib "") (part "CMP-04776-000041-1_2"))
    )
    (comp (ref "J25")
      (value "43650-0320")
      (footprint "CONN HEADER VERT 3POS 3MM")
      (description "CONN HEADER VERT 3POS 3MM")
      (fields
        (field (name "MANUFACTURER") "Molex")
        (field (name "OCTOPART") "https://octopart.com/43650-0320-molex-7670312")
      )
      (libsource (lib "Schematic Library - AJMG 2550XD Silver Jubilee") (part "CMP-04776-000004-1"))
    )
    (comp (ref "J26")
      (value "43650-0320")
      (footprint "CONN HEADER VERT 3POS 3MM")
      (description "CONN HEADER VERT 3POS 3MM")
      (fields
        (field (name "MANUFACTURER") "Molex")
        (field (name "OCTOPART") "https://octopart.com/43650-0320-molex-7670312")
      )
      (libsource (lib "") (part "CMP-04776-000004-1_2"))
    )
    (comp (ref "J27")
      (value "43650-0320")
      (footprint "CONN HEADER VERT 3POS 3MM")
      (description "CONN HEADER VERT 3POS 3MM")
      (fields
        (field (name "MANUFACTURER") "Molex")
        (field (name "OCTOPART") "https://octopart.com/43650-0320-molex-7670312")
      )
      (libsource (lib "") (part "CMP-04776-000004-1_2"))
    )
    (comp (ref "J28")
      (value "43650-0229")
      (footprint "CONN HEADER VERT 2POS 3MM")
      (description "CONN HEADER VERT 2POS 3MM")
      (fields
        (field (name "OCTOPART") "https://octopart.com/43650-0229-molex-7652326")
        (field (name "MANUFACTURER") "Molex")
      )
      (libsource (lib "Schematic Library - AJMG 2550XD Silver Jubilee") (part "CMP-04776-000041-1"))
    )
    (comp (ref "J29")
      (value "43650-0229")
      (footprint "CONN HEADER VERT 2POS 3MM")
      (description "CONN HEADER VERT 2POS 3MM")
      (fields
        (field (name "OCTOPART") "https://octopart.com/43650-0229-molex-7652326")
        (field (name "MANUFACTURER") "Molex")
      )
      (libsource (lib "Schematic Library - AJMG 2550XD Silver Jubilee") (part "CMP-04776-000041-1"))
    )
    (comp (ref "J30")
      (value "43650-0229")
      (footprint "CONN HEADER VERT 2POS 3MM")
      (description "CONN HEADER VERT 2POS 3MM")
      (fields
        (field (name "OCTOPART") "https://octopart.com/43650-0229-molex-7652326")
        (field (name "MANUFACTURER") "Molex")
      )
      (libsource (lib "Schematic Library - AJMG 2550XD Silver Jubilee") (part "CMP-04776-000041-1"))
    )
    (comp (ref "J31")
      (value "43650-0229")
      (footprint "CONN HEADER VERT 2POS 3MM")
      (description "CONN HEADER VERT 2POS 3MM")
      (fields
        (field (name "OCTOPART") "https://octopart.com/43650-0229-molex-7652326")
        (field (name "MANUFACTURER") "Molex")
      )
      (libsource (lib "Schematic Library - AJMG 2550XD Silver Jubilee") (part "CMP-04776-000041-1"))
    )
    (comp (ref "J32")
      (value "43650-0320")
      (footprint "CONN HEADER VERT 3POS 3MM")
      (description "CONN HEADER VERT 3POS 3MM")
      (fields
        (field (name "MANUFACTURER") "Molex")
        (field (name "OCTOPART") "https://octopart.com/43650-0320-molex-7670312")
      )
      (libsource (lib "") (part "CMP-04776-000004-1_1"))
    )
    (comp (ref "J33")
      (value "43650-0229")
      (footprint "CONN HEADER VERT 2POS 3MM")
      (description "CONN HEADER VERT 2POS 3MM")
      (fields
        (field (name "OCTOPART") "https://octopart.com/43650-0229-molex-7652326")
        (field (name "MANUFACTURER") "Molex")
      )
      (libsource (lib "Schematic Library - AJMG 2550XD Silver Jubilee") (part "CMP-04776-000041-1"))
    )
    (comp (ref "K1")
      (value "9-1393792-3")
      (footprint "RELAY_V23105A5301A201")
      (description "RELAY TELECOM DPDT 3A 5V")
      (fields
        (field (name "MANUFACTURER") "TE Connectivity")
        (field (name "OCTOPART") "https://octopart.com/9-1393792-3-te+connectivity-41192813")
      )
      (libsource (lib "Schematic Library - AJMG 2550XD Silver Jubilee") (part "CMP-03395-000111-1"))
    )
    (comp (ref "K2")
      (value "9-1393792-3")
      (footprint "RELAY_V23105A5301A201")
      (description "RELAY TELECOM DPDT 3A 5V")
      (fields
        (field (name "MANUFACTURER") "TE Connectivity")
        (field (name "OCTOPART") "https://octopart.com/9-1393792-3-te+connectivity-41192813")
      )
      (libsource (lib "Schematic Library - AJMG 2550XD Silver Jubilee") (part "CMP-03395-000111-1"))
    )
    (comp (ref "P1")
      (value "22-27-2021")
      (footprint "MOLX-22-27-2021_V")
      (fields (field (name "MANUFACTURER") "Molex") (field (name "PARTNUMBER") "0022272021"))
      (libsource (lib "Altium Content Vault") (part "CN-1P-M-R2"))
    )
    (comp (ref "P2")
      (value "22-27-2021")
      (footprint "MOLX-22-27-2021_V")
      (fields (field (name "MANUFACTURER") "Molex") (field (name "PARTNUMBER") "0022272021"))
      (libsource (lib "Altium Content Vault") (part "CN-1P-M-R2"))
    )
    (comp (ref "R1")
      (value "100k 1%")
      (footprint "R_2010")
      (description "RES SMD 2010 100K 1% 1W")
      (fields
        (field (name "MANUFACTURER") "Bourns")
        (field (name "MANUFACTURER PART NUMBER") "CMP2010-FX-1003ELF")
      )
      (libsource (lib "Schematic Library - AJMG 2550XD Silver Jubilee") (part "CMP2010-FX-1003ELF"))
    )
    (comp (ref "R2")
      (value "100k 1%")
      (footprint "R_2010")
      (description "RES SMD 2010 100K 1% 1W")
      (fields
        (field (name "MANUFACTURER") "Bourns")
        (field (name "MANUFACTURER PART NUMBER") "CMP2010-FX-1003ELF")
      )
      (libsource (lib "Schematic Library - AJMG 2550XD Silver Jubilee") (part "CMP2010-FX-1003ELF"))
    )
    (comp (ref "R3")
      (value "100k 1%")
      (footprint "R_2010")
      (description "RES SMD 2010 100K 1% 1W")
      (fields
        (field (name "MANUFACTURER") "Bourns")
        (field (name "MANUFACTURER PART NUMBER") "CMP2010-FX-1003ELF")
      )
      (libsource (lib "Schematic Library - AJMG 2550XD Silver Jubilee") (part "CMP2010-FX-1003ELF"))
    )
    (comp (ref "R4")
      (value "470k 1%")
      (footprint "R_2010")
      (description "RES SMD 2010 470K 1% 1W")
      (libsource (lib "Schematic Library - AJMG 2550XD Silver Jubilee") (part "CRM2010-FX-4703ELF"))
    )
    (comp (ref "R5")
      (value "100k 1%")
      (footprint "R_2010")
      (description "RES SMD 2010 100K 1% 1W")
      (fields
        (field (name "MANUFACTURER") "Bourns")
        (field (name "MANUFACTURER PART NUMBER") "CMP2010-FX-1003ELF")
      )
      (libsource (lib "Schematic Library - AJMG 2550XD Silver Jubilee") (part "CMP2010-FX-1003ELF"))
    )
    (comp (ref "R6")
      (value "10k 5%")
      (footprint "R_2512")
      (description "RES SMD 2512 10K 5% 3W")
      (fields
        (field (name "MANUFACTURER") "Bourns")
        (field (name "MANUFACTURER PART NUMBER") "CHP2512-JW-103ELF")
      )
      (libsource (lib "Schematic Library - AJMG 2550XD Silver Jubilee") (part "CHP2512-JW-103ELF"))
    )
    (comp (ref "R7")
      (value "47k 1%")
      (footprint "R_2512")
      (description "RES SMD 2512 47K 1% 1.5W")
      (fields
        (field (name "MANUFACTURER") "Bourns")
        (field (name "MANUFACTURER PART NUMBER") "CMP2512-FX-4702ELF")
      )
      (libsource (lib "Schematic Library - AJMG 2550XD Silver Jubilee") (part "CMP2512-FX-4702ELF"))
    )
    (comp (ref "R8")
      (value "100k 1%")
      (footprint "R_2010")
      (description "RES SMD 2010 100K 1% 1W")
      (fields
        (field (name "MANUFACTURER") "Bourns")
        (field (name "MANUFACTURER PART NUMBER") "CMP2010-FX-1003ELF")
      )
      (libsource (lib "Schematic Library - AJMG 2550XD Silver Jubilee") (part "CMP2010-FX-1003ELF"))
    )
    (comp (ref "R9")
      (value "1M 1%")
      (footprint "R_2010")
      (description "RES SMD 2010 1M 1% 1W")
      (fields
        (field (name "MANUFACTURER") "Bourns")
        (field (name "MANUFACTURER PART NUMBER") "CMP2010-FX-1004ELF")
      )
      (libsource (lib "Schematic Library - AJMG 2550XD Silver Jubilee") (part "CMP2010-FX-1004ELF"))
    )
    (comp (ref "R10")
      (value "220k 1%")
      (footprint "R_2010")
      (description "RES SMD 2010 220K 1% 1/2W")
      (fields
        (field (name "MANUFACTURER") "Bourns JW Miller")
        (field (name "MANUFACTURER PART NUMBER") "CHV2010-FX-2203ELF")
      )
      (libsource (lib "Schematic Library - AJMG 2550XD Silver Jubilee") (part "CHV2010-FX-2203ELF"))
    )
    (comp (ref "R11")
      (value "47k 1%")
      (footprint "R_2512")
      (description "RES SMD 2512 47K 1% 1.5W")
      (fields
        (field (name "MANUFACTURER") "Bourns")
        (field (name "MANUFACTURER PART NUMBER") "CMP2512-FX-4702ELF")
      )
      (libsource (lib "Schematic Library - AJMG 2550XD Silver Jubilee") (part "CMP2512-FX-4702ELF"))
    )
    (comp (ref "R12")
      (value "68k 2%")
      (footprint "R_MELF_0204")
      (description "RES SMD 0204 68K 2% 400mW")
      (fields
        (field (name "MANUFACTURER") "Vishay Beyschlag")
        (field (name "MANUFACTURER PART NUMBER") "CMA02040X6802GB300")
      )
      (libsource (lib "Schematic Library - AJMG 2550XD Silver Jubilee") (part "CMA02040X6802GB300"))
    )
    (comp (ref "R13")
      (value "10k 5%")
      (footprint "R_2512")
      (description "RES SMD 2512 10K 5% 3W")
      (fields
        (field (name "MANUFACTURER") "Bourns")
        (field (name "MANUFACTURER PART NUMBER") "CHP2512-JW-103ELF")
      )
      (libsource (lib "Schematic Library - AJMG 2550XD Silver Jubilee") (part "CHP2512-JW-103ELF"))
    )
    (comp (ref "R14")
      (value "100k 1%")
      (footprint "R_2010")
      (description "RES SMD 2010 100K 1% 1W")
      (fields
        (field (name "MANUFACTURER") "Bourns")
        (field (name "MANUFACTURER PART NUMBER") "CMP2010-FX-1003ELF")
      )
      (libsource (lib "Schematic Library - AJMG 2550XD Silver Jubilee") (part "CMP2010-FX-1003ELF"))
    )
    (comp (ref "R15")
      (value "100k 1%")
      (footprint "R_2010")
      (description "RES SMD 2010 100K 1% 1W")
      (fields
        (field (name "MANUFACTURER") "Bourns")
        (field (name "MANUFACTURER PART NUMBER") "CMP2010-FX-1003ELF")
      )
      (libsource (lib "Schematic Library - AJMG 2550XD Silver Jubilee") (part "CMP2010-FX-1003ELF"))
    )
    (comp (ref "R16")
      (value "47k 1%")
      (footprint "R_2512")
      (description "RES SMD 2512 47K 1% 1.5W")
      (fields
        (field (name "MANUFACTURER") "Bourns")
        (field (name "MANUFACTURER PART NUMBER") "CMP2512-FX-4702ELF")
      )
      (libsource (lib "Schematic Library - AJMG 2550XD Silver Jubilee") (part "CMP2512-FX-4702ELF"))
    )
    (comp (ref "R17")
      (value "10k 1%")
      (footprint "R_2010")
      (description "RES SMD 2010 10K 1% 1W")
      (fields
        (field (name "MANUFACTURER") "Bourns")
        (field (name "MANUFACTURER PART NUMBER") "CMP2010-FX-1002ELF")
      )
      (libsource (lib "Schematic Library - AJMG 2550XD Silver Jubilee") (part "CMP2010-FX-1002ELF"))
    )
    (comp (ref "R18")
      (value "22k 5%")
      (footprint "R_2512")
      (description "RES SMD 2512 22K 5% 1W")
      (fields
        (field (name "MANUFACTURER") "Bourns")
        (field (name "MANUFACTURER PART NUMBER") "CR2512-JW-223ELF")
      )
      (libsource (lib "Schematic Library - AJMG 2550XD Silver Jubilee") (part "CR2512-JW-223ELF"))
    )
    (comp (ref "R19")
      (value "1M 1%")
      (footprint "R_2010")
      (description "RES SMD 2010 1M 1% 1W")
      (fields
        (field (name "MANUFACTURER") "Bourns")
        (field (name "MANUFACTURER PART NUMBER") "CMP2010-FX-1004ELF")
      )
      (libsource (lib "Schematic Library - AJMG 2550XD Silver Jubilee") (part "CMP2010-FX-1004ELF"))
    )
    (comp (ref "R20")
      (value "10k 1%")
      (footprint "R_2010")
      (description "RES SMD 2010 10K 1% 1W")
      (fields
        (field (name "MANUFACTURER") "Bourns")
        (field (name "MANUFACTURER PART NUMBER") "CMP2010-FX-1002ELF")
      )
      (libsource (lib "Schematic Library - AJMG 2550XD Silver Jubilee") (part "CMP2010-FX-1002ELF"))
    )
    (comp (ref "R21")
      (value "10R 5%")
      (footprint "R_2616_MOLDED")
      (description "RES SMD 2616 10R 5% 2W SMW2")
      (fields
        (field (name "MANUFACTURER") "TE Connectivity")
        (field (name "MANUFACTURER PART NUMBER") "SMW210RJT")
      )
      (libsource (lib "Schematic Library - AJMG 2550XD Silver Jubilee") (part "SMW210RJT"))
    )
    (comp (ref "R22")
      (value "220k 1%")
      (footprint "R_2010")
      (description "RES SMD 2010 220K 1% 1/2W")
      (fields
        (field (name "MANUFACTURER") "Bourns JW Miller")
        (field (name "MANUFACTURER PART NUMBER") "CHV2010-FX-2203ELF")
      )
      (libsource (lib "Schematic Library - AJMG 2550XD Silver Jubilee") (part "CHV2010-FX-2203ELF"))
    )
    (comp (ref "R23")
      (value "1.5k 5%")
      (footprint "R_2512")
      (description "RES SMD 2512 1.5k 5% 1W")
      (fields
        (field (name "MANUFACTURER") "Bourns")
        (field (name "MANUFACTURER PART NUMBER") "CR2512-JW-152ELF")
      )
      (libsource (lib "Schematic Library - AJMG 2550XD Silver Jubilee") (part "CR2512-JW-152ELF"))
    )
    (comp (ref "R24")
      (value "2.7k 1%")
      (footprint "R_2512")
      (description "RES SMD 2512 2.7K 1% 1.5W")
      (fields
        (field (name "MANUFACTURER") "Bourns")
        (field (name "MANUFACTURER PART NUMBER") "CMP2512AFX-2701ELF")
      )
      (libsource (lib "Schematic Library - AJMG 2550XD Silver Jubilee") (part "CMP2512AFX-2701ELF"))
    )
    (comp (ref "R25")
      (value "1.5k 5%")
      (footprint "R_2512")
      (description "RES SMD 2512 1.5k 5% 1W")
      (fields
        (field (name "MANUFACTURER") "Bourns")
        (field (name "MANUFACTURER PART NUMBER") "CR2512-JW-152ELF")
      )
      (libsource (lib "Schematic Library - AJMG 2550XD Silver Jubilee") (part "CR2512-JW-152ELF"))
    )
    (comp (ref "R26")
      (value "220k 1%")
      (footprint "R_2010")
      (description "RES SMD 2010 220K 1% 1/2W")
      (fields
        (field (name "MANUFACTURER") "Bourns JW Miller")
        (field (name "MANUFACTURER PART NUMBER") "CHV2010-FX-2203ELF")
      )
      (libsource (lib "Schematic Library - AJMG 2550XD Silver Jubilee") (part "CHV2010-FX-2203ELF"))
    )
    (comp (ref "R27")
      (value "1k2")
      (footprint "R_2512")
      (description "RES SMD 2512 1.2k 5% 1W")
      (fields
        (field (name "MANUFACTURER") "Bourns")
        (field (name "MANUFACTURER PART NUMBER") "CR2512-JW-122ELF")
      )
      (libsource (lib "Schematic Library - AJMG 2550XD Silver Jubilee") (part "CR2512-JW-122ELF"))
    )
    (comp (ref "R28")
      (value "3k 1%")
      (footprint "R_2512")
      (description "RES SMD 2512 3k 1% 1W")
      (fields
        (field (name "MANUFACTURER") "Bourns")
        (field (name "MANUFACTURER PART NUMBER") "CR2512-FX-3001ELF")
      )
      (libsource (lib "Schematic Library - AJMG 2550XD Silver Jubilee") (part "CR2512-FX-3001ELF"))
    )
    (comp (ref "R29")
      (value "330R 2%")
      (footprint "R_MELF_0207")
      (description "RES SMD 0207 330R 2% 1W")
      (fields
        (field (name "MANUFACTURER") "Vishay Beyschlag")
        (field (name "MANUFACTURER PART NUMBER") "CMB02070X3300GB200")
      )
      (libsource (lib "Schematic Library - AJMG 2550XD Silver Jubilee") (part "CMB02070X3300GB200"))
    )
    (comp (ref "R30")
      (value "330R 2%")
      (footprint "R_MELF_0207")
      (description "RES SMD 0207 330R 2% 1W")
      (fields
        (field (name "MANUFACTURER") "Vishay Beyschlag")
        (field (name "MANUFACTURER PART NUMBER") "CMB02070X3300GB200")
      )
      (libsource (lib "Schematic Library - AJMG 2550XD Silver Jubilee") (part "CMB02070X3300GB200"))
    )
    (comp (ref "R31")
      (value "5.6k 5%")
      (footprint "R_2512")
      (description "RES SMD 2512 5.6K 5% 1W")
      (fields
        (field (name "MANUFACTURER") "Bourns")
        (field (name "MANUFACTURER PART NUMBER") "CR2512-JW-562ELF")
      )
      (libsource (lib "Schematic Library - AJMG 2550XD Silver Jubilee") (part "CR2512-JW-562ELF"))
    )
    (comp (ref "R32")
      (value "220k 1%")
      (footprint "R_2010")
      (description "RES SMD 2010 220K 1% 1/2W")
      (fields
        (field (name "MANUFACTURER") "Bourns JW Miller")
        (field (name "MANUFACTURER PART NUMBER") "CHV2010-FX-2203ELF")
      )
      (libsource (lib "Schematic Library - AJMG 2550XD Silver Jubilee") (part "CHV2010-FX-2203ELF"))
    )
    (comp (ref "R33")
      (value "1K 1%")
      (footprint "R_3550")
      (description "RES SMD 3550 1K 1% 5W")
      (fields
        (field (name "MANUFACTURER") "TE Connectivity")
        (field (name "MANUFACTURER PART NUMBER") "35501K0FT")
      )
      (libsource (lib "Schematic Library - AJMG 2550XD Silver Jubilee") (part "35501K0FT"))
    )
    (comp (ref "R34")
      (value "1M 1%")
      (footprint "R_2010")
      (description "RES SMD 2010 1M 1% 1W")
      (fields
        (field (name "MANUFACTURER") "Bourns")
        (field (name "MANUFACTURER PART NUMBER") "CMP2010-FX-1004ELF")
      )
      (libsource (lib "Schematic Library - AJMG 2550XD Silver Jubilee") (part "CMP2010-FX-1004ELF"))
    )
    (comp (ref "R35")
      (value "82k 5%")
      (footprint "R_2512")
      (description "RES SMD 2512 82K 5% 2W")
      (fields
        (field (name "MANUFACTURER") "Bourns")
        (field (name "MANUFACTURER PART NUMBER") "CRM2512-JW-823ELF")
      )
      (libsource (lib "Schematic Library - AJMG 2550XD Silver Jubilee") (part "CRM2512-JW-823ELF"))
    )
    (comp (ref "R36")
      (value "220k 1%")
      (footprint "R_2010")
      (description "RES SMD 2010 220K 1% 1/2W")
      (fields
        (field (name "MANUFACTURER") "Bourns JW Miller")
        (field (name "MANUFACTURER PART NUMBER") "CHV2010-FX-2203ELF")
      )
      (libsource (lib "Schematic Library - AJMG 2550XD Silver Jubilee") (part "CHV2010-FX-2203ELF"))
    )
    (comp (ref "R37")
      (value "1R 1%")
      (footprint "R_4527_MOLDED")
      (description "RES SMD 4527 1R 1% 2W")
      (fields
        (field (name "MANUFACTURER") "Vishay Dale")
        (field (name "MANUFACTURER PART NUMBER") "WSC00021R000FEA")
      )
      (libsource (lib "Schematic Library - AJMG 2550XD Silver Jubilee") (part "WSC00021R000FEA"))
    )
    (comp (ref "R38")
      (value "100k 1%")
      (footprint "R_2010")
      (description "RES SMD 2010 100K 1% 1W")
      (fields
        (field (name "MANUFACTURER") "Bourns")
        (field (name "MANUFACTURER PART NUMBER") "CMP2010-FX-1003ELF")
      )
      (libsource (lib "Schematic Library - AJMG 2550XD Silver Jubilee") (part "CMP2010-FX-1003ELF"))
    )
    (comp (ref "R39")
      (value "100k 1%")
      (footprint "R_2010")
      (description "RES SMD 2010 100K 1% 1W")
      (fields
        (field (name "MANUFACTURER") "Bourns")
        (field (name "MANUFACTURER PART NUMBER") "CMP2010-FX-1003ELF")
      )
      (libsource (lib "Schematic Library - AJMG 2550XD Silver Jubilee") (part "CMP2010-FX-1003ELF"))
    )
    (comp (ref "R40")
      (value "1R 1%")
      (footprint "R_4527_MOLDED")
      (description "RES SMD 4527 1R 1% 2W")
      (fields
        (field (name "MANUFACTURER") "Vishay Dale")
        (field (name "MANUFACTURER PART NUMBER") "WSC00021R000FEA")
      )
      (libsource (lib "Schematic Library - AJMG 2550XD Silver Jubilee") (part "WSC00021R000FEA"))
    )
    (comp (ref "R41")
      (value "330R 2%")
      (footprint "R_MELF_0207")
      (description "RES SMD 0207 330R 2% 1W")
      (fields
        (field (name "MANUFACTURER") "Vishay Beyschlag")
        (field (name "MANUFACTURER PART NUMBER") "CMB02070X3300GB200")
      )
      (libsource (lib "Schematic Library - AJMG 2550XD Silver Jubilee") (part "CMB02070X3300GB200"))
    )
    (comp (ref "R42")
      (value "330R 2%")
      (footprint "R_MELF_0207")
      (description "RES SMD 0207 330R 2% 1W")
      (fields
        (field (name "MANUFACTURER") "Vishay Beyschlag")
        (field (name "MANUFACTURER PART NUMBER") "CMB02070X3300GB200")
      )
      (libsource (lib "Schematic Library - AJMG 2550XD Silver Jubilee") (part "CMB02070X3300GB200"))
    )
    (comp (ref "R43")
      (value "10k 1%")
      (footprint "R_2010")
      (description "RES SMD 2010 10K 1% 1W")
      (fields
        (field (name "MANUFACTURER") "Bourns")
        (field (name "MANUFACTURER PART NUMBER") "CMP2010-FX-1002ELF")
      )
      (libsource (lib "Schematic Library - AJMG 2550XD Silver Jubilee") (part "CMP2010-FX-1002ELF"))
    )
    (comp (ref "R44")
      (value "470R 1%")
      (footprint "R_2512")
      (description "RES SMD 2512 470R 1% 2W")
      (fields
        (field (name "MANUFACTURER") "Bourns")
        (field (name "MANUFACTURER PART NUMBER") "CRM2512-FX-4700ELF")
      )
      (libsource (lib "Schematic Library - AJMG 2550XD Silver Jubilee") (part "CRM2512-FX-4700ELF"))
    )
    (comp (ref "R45")
      (value "100k 1%")
      (footprint "R_2010")
      (description "RES SMD 2010 100K 1% 1W")
      (fields
        (field (name "MANUFACTURER") "Bourns")
        (field (name "MANUFACTURER PART NUMBER") "CMP2010-FX-1003ELF")
      )
      (libsource (lib "Schematic Library - AJMG 2550XD Silver Jubilee") (part "CMP2010-FX-1003ELF"))
    )
    (comp (ref "R46")
      (value "220k 1%")
      (footprint "R_2010")
      (description "RES SMD 2010 220K 1% 1/2W")
      (fields
        (field (name "MANUFACTURER") "Bourns JW Miller")
        (field (name "MANUFACTURER PART NUMBER") "CHV2010-FX-2203ELF")
      )
      (libsource (lib "Schematic Library - AJMG 2550XD Silver Jubilee") (part "CHV2010-FX-2203ELF"))
    )
    (comp (ref "R47")
      (value "10k 1%")
      (footprint "R_2010")
      (description "RES SMD 2010 10K 1% 1W")
      (fields
        (field (name "MANUFACTURER") "Bourns")
        (field (name "MANUFACTURER PART NUMBER") "CMP2010-FX-1002ELF")
      )
      (libsource (lib "Schematic Library - AJMG 2550XD Silver Jubilee") (part "CMP2010-FX-1002ELF"))
    )
    (comp (ref "R48")
      (value "1K 1%")
      (footprint "R_3550")
      (description "RES SMD 3550 1K 1% 5W")
      (fields
        (field (name "MANUFACTURER") "TE Connectivity")
        (field (name "MANUFACTURER PART NUMBER") "35501K0FT")
      )
      (libsource (lib "Schematic Library - AJMG 2550XD Silver Jubilee") (part "35501K0FT"))
    )
    (comp (ref "R49")
      (value "1M 1%")
      (footprint "R_2010")
      (description "RES SMD 2010 1M 1% 1W")
      (fields
        (field (name "MANUFACTURER") "Bourns")
        (field (name "MANUFACTURER PART NUMBER") "CMP2010-FX-1004ELF")
      )
      (libsource (lib "Schematic Library - AJMG 2550XD Silver Jubilee") (part "CMP2010-FX-1004ELF"))
    )
    (comp (ref "R50")
      (value "5.6k 5%")
      (footprint "R_2512")
      (description "RES SMD 2512 5.6K 5% 1W")
      (fields
        (field (name "MANUFACTURER") "Bourns")
        (field (name "MANUFACTURER PART NUMBER") "CR2512-JW-562ELF")
      )
      (libsource (lib "Schematic Library - AJMG 2550XD Silver Jubilee") (part "CR2512-JW-562ELF"))
    )
    (comp (ref "R51")
      (value "100k 1%")
      (footprint "R_2010")
      (description "RES SMD 2010 100K 1% 1W")
      (fields
        (field (name "MANUFACTURER") "Bourns")
        (field (name "MANUFACTURER PART NUMBER") "CMP2010-FX-1003ELF")
      )
      (libsource (lib "Schematic Library - AJMG 2550XD Silver Jubilee") (part "CMP2010-FX-1003ELF"))
    )
    (comp (ref "R52")
      (value "1M 1%")
      (footprint "R_2010")
      (description "RES SMD 2010 1M 1% 1W")
      (fields
        (field (name "MANUFACTURER") "Bourns")
        (field (name "MANUFACTURER PART NUMBER") "CMP2010-FX-1004ELF")
      )
      (libsource (lib "Schematic Library - AJMG 2550XD Silver Jubilee") (part "CMP2010-FX-1004ELF"))
    )
    (comp (ref "R53")
      (value "100k 1%")
      (footprint "R_2010")
      (description "RES SMD 2010 100K 1% 1W")
      (fields
        (field (name "MANUFACTURER") "Bourns")
        (field (name "MANUFACTURER PART NUMBER") "CMP2010-FX-1003ELF")
      )
      (libsource (lib "Schematic Library - AJMG 2550XD Silver Jubilee") (part "CMP2010-FX-1003ELF"))
    )
    (comp (ref "R54")
      (value "470R 1%")
      (footprint "R_2512")
      (description "RES SMD 2512 470R 1% 2W")
      (fields
        (field (name "MANUFACTURER") "Bourns")
        (field (name "MANUFACTURER PART NUMBER") "CRM2512-FX-4700ELF")
      )
      (libsource (lib "Schematic Library - AJMG 2550XD Silver Jubilee") (part "CRM2512-FX-4700ELF"))
    )
    (comp (ref "R55")
      (value "100k 1%")
      (footprint "R_2010")
      (description "RES SMD 2010 100K 1% 1W")
      (fields
        (field (name "MANUFACTURER") "Bourns")
        (field (name "MANUFACTURER PART NUMBER") "CMP2010-FX-1003ELF")
      )
      (libsource (lib "Schematic Library - AJMG 2550XD Silver Jubilee") (part "CMP2010-FX-1003ELF"))
    )
    (comp (ref "R56")
      (value "470R 1%")
      (footprint "R_2512")
      (description "RES SMD 2512 470R 1% 2W")
      (fields
        (field (name "MANUFACTURER") "Bourns")
        (field (name "MANUFACTURER PART NUMBER") "CRM2512-FX-4700ELF")
      )
      (libsource (lib "Schematic Library - AJMG 2550XD Silver Jubilee") (part "CRM2512-FX-4700ELF"))
    )
    (comp (ref "R57")
      (value "4k7 5%")
      (footprint "R_2512_N")
      (description "RES SMD 2512 4.7k 5% 1W")
      (fields (field (name "TOLERANCE") "5 %") (field (name "POWER") "1 W"))
      (libsource (lib "Schematic Library - AJMG 2550XD Silver Jubilee") (part "CMP-1018-00090-1"))
    )
    (comp (ref "V1")
      (value "ECC83")
      (footprint "VT9-PT-2")
      (libsource (lib "Schematic Library - AJMG 2550XD Silver Jubilee") (part "ECC83"))
    )
    (comp (ref "V2")
      (value "ECC83")
      (footprint "VT9-PT-2")
      (libsource (lib "Schematic Library - AJMG 2550XD Silver Jubilee") (part "ECC83"))
    )
    (comp (ref "V3")
      (value "12DW7")
      (footprint "VT9-PT-2")
      (libsource (lib "Schematic Library - AJMG 2550XD Silver Jubilee") (part "12DW7"))
    )
    (comp (ref "V4") (value "EL34") (footprint "VT8-PT-2") (libsource (lib "") (part "EL34_1")))
    (comp (ref "V5") (value "ECC83") (footprint "VT9-PT-2") (libsource (lib "") (part "ECC83_1")))
    (comp (ref "V6")
      (value "EL34")
      (footprint "VT8-PT-2")
      (libsource (lib "Schematic Library - AJMG 2550XD Silver Jubilee") (part "EL34"))
    )
  )
  (nets
    (net (code "1") (name "/FS_CHA") (class "Default")
      (node (ref "C19") (pin "1") (pinfunction "P_1") (pintype "passive"))
      (node (ref "D8") (pin "2") (pinfunction "C_2") (pintype "passive"))
      (node (ref "J13") (pin "2") (pinfunction "2_2") (pintype "passive"))
      (node (ref "K1") (pin "16") (pinfunction "16_16") (pintype "passive"))
      (node (ref "R30") (pin "2") (pinfunction "2_2") (pintype "passive"))
    )
    (net (code "2") (name "/FS_JS1") (class "Default")
      (node (ref "J15") (pin "1") (pinfunction "1_1") (pintype "passive"))
      (node (ref "J16") (pin "2") (pinfunction "2_2") (pintype "passive"))
    )
    (net (code "3") (name "/FS_JS2") (class "Default")
      (node (ref "J15") (pin "2") (pinfunction "2_2") (pintype "passive"))
      (node (ref "J24") (pin "1") (pinfunction "1_1") (pintype "passive"))
    )
    (net (code "4") (name "/FS_REV") (class "Default")
      (node (ref "C27") (pin "1") (pinfunction "P_1") (pintype "passive"))
      (node (ref "D10") (pin "2") (pinfunction "C_2") (pintype "passive"))
      (node (ref "J13") (pin "1") (pinfunction "1_1") (pintype "passive"))
      (node (ref "K2") (pin "16") (pinfunction "16_16") (pintype "passive"))
      (node (ref "R42") (pin "2") (pinfunction "2_2") (pintype "passive"))
    )
    (net (code "5") (name "/FX_LOOP") (class "Default")
      (node (ref "J22") (pin "2") (pinfunction "2_2") (pintype "passive"))
      (node (ref "J6") (pin "1") (pinfunction "1_1") (pintype "passive"))
      (node (ref "R20") (pin "2") (pinfunction "2_2") (pintype "passive"))
      (node (ref "R8") (pin "1") (pinfunction "1_1") (pintype "passive"))
    )
    (net (code "6") (name "/RELAY3") (class "Default")
      (node (ref "C3") (pin "2") (pinfunction "2_2") (pintype "passive"))
      (node (ref "K1") (pin "4") (pinfunction "4_4") (pintype "passive"))
      (node (ref "R14") (pin "1") (pinfunction "1_1") (pintype "passive"))
    )
    (net (code "7") (name "/RELAY5") (class "Default")
      (node (ref "J10") (pin "2") (pinfunction "2_2") (pintype "passive"))
      (node (ref "K1") (pin "6") (pinfunction "6_6") (pintype "passive"))
    )
    (net (code "8") (name "/RELAY6") (class "Default")
      (node (ref "J4") (pin "2") (pinfunction "2_2") (pintype "passive"))
      (node (ref "K1") (pin "8") (pinfunction "8_8") (pintype "passive"))
    )
    (net (code "9") (name "/RELAY7") (class "Default")
      (node (ref "C13") (pin "2") (pinfunction "2_2") (pintype "passive"))
      (node (ref "D1") (pin "1") (pinfunction "A_1") (pintype "passive"))
      (node (ref "D2") (pin "2") (pinfunction "C_2") (pintype "passive"))
      (node (ref "J5") (pin "1") (pinfunction "1_1") (pintype "passive"))
      (node (ref "K1") (pin "9") (pinfunction "9_9") (pintype "passive"))
      (node (ref "R7") (pin "2") (pinfunction "2_2") (pintype "passive"))
    )
    (net (code "10") (name "/RELAY8") (class "Default")
      (node (ref "J12") (pin "1") (pinfunction "1_1") (pintype "passive"))
      (node (ref "K1") (pin "11") (pinfunction "11_11") (pintype "passive"))
      (node (ref "R10") (pin "1") (pinfunction "1_1") (pintype "passive"))
      (node (ref "R17") (pin "2") (pinfunction "2_2") (pintype "passive"))
      (node (ref "R22") (pin "1") (pinfunction "1_1") (pintype "passive"))
    )
    (net (code "11") (name "/REVERB_SW") (class "Default")
      (node (ref "K2") (pin "4") (pinfunction "4_4") (pintype "passive"))
      (node (ref "R13") (pin "1") (pinfunction "1_1") (pintype "passive"))
      (node (ref "R18") (pin "2") (pinfunction "2_2") (pintype "passive"))
      (node (ref "V3") (pin "7") (pinfunction "G1_7") (pintype "passive"))
    )
    (net (code "12") (name "/REV_IN1") (class "Default")
      (node (ref "C23") (pin "1") (pinfunction "1_1") (pintype "passive"))
      (node (ref "C26") (pin "2") (pinfunction "2_2") (pintype "passive"))
      (node (ref "J9") (pin "1") (pinfunction "1_1") (pintype "passive"))
      (node (ref "R32") (pin "1") (pinfunction "1_1") (pintype "passive"))
      (node (ref "V2") (pin "1") (pinfunction "A2_1") (pintype "passive"))
    )
    (net (code "13") (name "/REV_IN2") (class "Default")
      (node (ref "J19") (pin "2") (pinfunction "2_2") (pintype "passive"))
      (node (ref "J21") (pin "1") (pinfunction "1_1") (pintype "passive"))
      (node (ref "J9") (pin "3") (pinfunction "3_3") (pintype "passive"))
    )
    (net (code "14") (name "/REV_OUT") (class "Default")
      (node (ref "C22") (pin "1") (pinfunction "1_1") (pintype "passive"))
      (node (ref "C6") (pin "2") (pinfunction "2_2") (pintype "passive"))
      (node (ref "R34") (pin "2") (pinfunction "2_2") (pintype "passive"))
      (node (ref "V5") (pin "7") (pinfunction "G1_7") (pintype "passive"))
    )
    (net (code "15") (name "B+0") (class "Default")
      (node (ref "J17") (pin "2") (pinfunction "2_2") (pintype "passive"))
      (node (ref "J32") (pin "3") (pinfunction "3_3") (pintype "passive"))
    )
    (net (code "16") (name "B+1") (class "Default")
      (node (ref "J14") (pin "3") (pinfunction "3_3") (pintype "passive"))
      (node (ref "J23") (pin "3") (pinfunction "3_3") (pintype "passive"))
      (node (ref "J31") (pin "1") (pinfunction "1_1") (pintype "passive"))
    )
    (net (code "17") (name "B+2") (class "Default")
      (node (ref "J30") (pin "1") (pinfunction "1_1") (pintype "passive"))
      (node (ref "R35") (pin "1") (pinfunction "1_1") (pintype "passive"))
      (node (ref "R45") (pin "2") (pinfunction "2_2") (pintype "passive"))
    )
    (net (code "18") (name "B+3") (class "Default")
      (node (ref "J29") (pin "1") (pinfunction "1_1") (pintype "passive"))
      (node (ref "R2") (pin "2") (pinfunction "2_2") (pintype "passive"))
      (node (ref "R32") (pin "2") (pinfunction "2_2") (pintype "passive"))
      (node (ref "R4") (pin "1") (pinfunction "1_1") (pintype "passive"))
      (node (ref "R6") (pin "2") (pinfunction "2_2") (pintype "passive"))
    )
    (net (code "19") (name "B+4") (class "Default")
      (node (ref "C1") (pin "2") (pinfunction "2_2") (pintype "passive"))
      (node (ref "J28") (pin "1") (pinfunction "1_1") (pintype "passive"))
      (node (ref "R1") (pin "2") (pinfunction "2_2") (pintype "passive"))
      (node (ref "R3") (pin "2") (pinfunction "2_2") (pintype "passive"))
    )
    (net (code "20") (name "BIAS") (class "Default")
      (node (ref "J32") (pin "2") (pinfunction "2_2") (pintype "passive"))
      (node (ref "R36") (pin "1") (pinfunction "1_1") (pintype "passive"))
      (node (ref "R46") (pin "2") (pinfunction "2_2") (pintype "passive"))
    )
    (net (code "21") (name "H1") (class "Default")
      (node (ref "C19") (pin "2") (pinfunction "N_2") (pintype "passive"))
      (node (ref "C20") (pin "2") (pinfunction "N_2") (pintype "passive"))
      (node (ref "C27") (pin "2") (pinfunction "N_2") (pintype "passive"))
      (node (ref "C28") (pin "2") (pinfunction "N_2") (pintype "passive"))
      (node (ref "D10") (pin "1") (pinfunction "A_1") (pintype "passive"))
      (node (ref "D8") (pin "1") (pinfunction "A_1") (pintype "passive"))
      (node (ref "J13") (pin "3") (pinfunction "3_3") (pintype "passive"))
      (node (ref "J16") (pin "1") (pinfunction "1_1") (pintype "passive"))
      (node (ref "J24") (pin "2") (pinfunction "2_2") (pintype "passive"))
      (node (ref "J33") (pin "1") (pinfunction "1_1") (pintype "passive"))
      (node (ref "R29") (pin "1") (pinfunction "1_1") (pintype "passive"))
      (node (ref "R41") (pin "1") (pinfunction "1_1") (pintype "passive"))
      (node (ref "V1") (pin "4") (pinfunction "FB_4") (pintype "passive"))
      (node (ref "V1") (pin "5") (pinfunction "FA_5") (pintype "passive"))
      (node (ref "V2") (pin "4") (pinfunction "FB_4") (pintype "passive"))
      (node (ref "V2") (pin "5") (pinfunction "FA_5") (pintype "passive"))
      (node (ref "V3") (pin "4") (pinfunction "FB_4") (pintype "passive"))
      (node (ref "V3") (pin "5") (pinfunction "FA_5") (pintype "passive"))
      (node (ref "V4") (pin "2") (pinfunction "F_2") (pintype "passive"))
      (node (ref "V5") (pin "4") (pinfunction "FB_4") (pintype "passive"))
      (node (ref "V5") (pin "5") (pinfunction "FA_5") (pintype "passive"))
      (node (ref "V6") (pin "7") (pinfunction "F_7") (pintype "passive"))
    )
    (net (code "22") (name "H2") (class "Default")
      (node (ref "D11") (pin "1") (pinfunction "A_1") (pintype "passive"))
      (node (ref "D9") (pin "1") (pinfunction "A_1") (pintype "passive"))
      (node (ref "J33") (pin "2") (pinfunction "2_2") (pintype "passive"))
      (node (ref "V1") (pin "9") (pinfunction "FC_9") (pintype "passive"))
      (node (ref "V2") (pin "9") (pinfunction "FC_9") (pintype "passive"))
      (node (ref "V3") (pin "9") (pinfunction "FC_9") (pintype "passive"))
      (node (ref "V4") (pin "7") (pinfunction "F_7") (pintype "passive"))
      (node (ref "V5") (pin "9") (pinfunction "FC_9") (pintype "passive"))
      (node (ref "V6") (pin "2") (pinfunction "F_2") (pintype "passive"))
    )
    (net (code "23") (name "Net-(C2-Pad2)") (class "Default")
      (node (ref "C2") (pin "2") (pinfunction "2_2") (pintype "passive"))
      (node (ref "C3") (pin "1") (pinfunction "1_1") (pintype "passive"))
      (node (ref "J10") (pin "1") (pinfunction "1_1") (pintype "passive"))
      (node (ref "J4") (pin "1") (pinfunction "1_1") (pintype "passive"))
    )
    (net (code "24") (name "Net-(C4-Pad2)") (class "Default")
      (node (ref "C4") (pin "2") (pinfunction "2_2") (pintype "passive"))
      (node (ref "R10") (pin "2") (pinfunction "2_2") (pintype "passive"))
      (node (ref "R7") (pin "1") (pinfunction "1_1") (pintype "passive"))
    )
    (net (code "25") (name "Net-(C5-Pad2)") (class "Default")
      (node (ref "C5") (pin "2") (pinfunction "2_2") (pintype "passive"))
      (node (ref "R8") (pin "2") (pinfunction "2_2") (pintype "passive"))
      (node (ref "R9") (pin "1") (pinfunction "1_1") (pintype "passive"))
    )
    (net (code "26") (name "Net-(C6-Pad1)") (class "Default")
      (node (ref "C6") (pin "1") (pinfunction "1_1") (pintype "passive"))
      (node (ref "R5") (pin "2") (pinfunction "2_2") (pintype "passive"))
    )
    (net (code "27") (name "Net-(C7-Pad2)") (class "Default")
      (node (ref "C7") (pin "2") (pinfunction "2_2") (pintype "passive"))
      (node (ref "J1") (pin "2") (pinfunction "2_2") (pintype "passive"))
    )
    (net (code "28") (name "Net-(C8-Pad2)") (class "Default")
      (node (ref "C8") (pin "2") (pinfunction "2_2") (pintype "passive"))
      (node (ref "J2") (pin "2") (pinfunction "2_2") (pintype "passive"))
    )
    (net (code "29") (name "Net-(C9-Pad1)") (class "Default")
      (node (ref "C9") (pin "1") (pinfunction "1_1") (pintype "passive"))
      (node (ref "J8") (pin "1") (pinfunction "1_1") (pintype "passive"))
    )
    (net (code "30") (name "Net-(C9-Pad2)") (class "Default")
      (node (ref "C9") (pin "2") (pinfunction "2_2") (pintype "passive"))
      (node (ref "R12") (pin "1") (pinfunction "1_1") (pintype "passive"))
      (node (ref "R19") (pin "2") (pinfunction "2_2") (pintype "passive"))
    )
    (net (code "31") (name "Net-(C11-Pad1)") (class "Default")
      (node (ref "C11") (pin "1") (pinfunction "1_1") (pintype "passive"))
      (node (ref "J11") (pin "1") (pinfunction "1_1") (pintype "passive"))
      (node (ref "J11") (pin "2") (pinfunction "2_2") (pintype "passive"))
    )
    (net (code "32") (name "Net-(C11-Pad2)") (class "Default")
      (node (ref "C11") (pin "2") (pinfunction "2_2") (pintype "passive"))
      (node (ref "J1") (pin "1") (pinfunction "1_1") (pintype "passive"))
      (node (ref "R5") (pin "1") (pinfunction "1_1") (pintype "passive"))
    )
    (net (code "33") (name "Net-(C12-Pad1)") (class "Default")
      (node (ref "C12") (pin "1") (pinfunction "1_1") (pintype "passive"))
      (node (ref "J7") (pin "3") (pinfunction "3_3") (pintype "passive"))
    )
    (net (code "34") (name "Net-(C12-Pad2)") (class "Default")
      (node (ref "C12") (pin "2") (pinfunction "2_2") (pintype "passive"))
      (node (ref "J9") (pin "2") (pinfunction "2_2") (pintype "passive"))
    )
    (net (code "35") (name "Net-(C14-P)") (class "Default")
      (node (ref "C10") (pin "1") (pinfunction "1_1") (pintype "passive"))
      (node (ref "C14") (pin "1") (pinfunction "P_1") (pintype "passive"))
      (node (ref "R24") (pin "2") (pinfunction "2_2") (pintype "passive"))
      (node (ref "V1") (pin "8") (pinfunction "K1_8") (pintype "passive"))
    )
    (net (code "36") (name "Net-(C15-P)") (class "Default")
      (node (ref "C15") (pin "1") (pinfunction "P_1") (pintype "passive"))
      (node (ref "R25") (pin "2") (pinfunction "2_2") (pintype "passive"))
      (node (ref "V1") (pin "3") (pinfunction "K2_3") (pintype "passive"))
    )
    (net (code "37") (name "Net-(C17-P)") (class "Default")
      (node (ref "C17") (pin "1") (pinfunction "P_1") (pintype "passive"))
      (node (ref "R27") (pin "2") (pinfunction "2_2") (pintype "passive"))
      (node (ref "V3") (pin "3") (pinfunction "K2_3") (pintype "passive"))
    )
    (net (code "38") (name "Net-(C20-P)") (class "Default")
      (node (ref "C20") (pin "1") (pinfunction "P_1") (pintype "passive"))
      (node (ref "D9") (pin "2") (pinfunction "C_2") (pintype "passive"))
      (node (ref "K1") (pin "1") (pinfunction "1_1") (pintype "passive"))
    )
    (net (code "39") (name "Net-(C21-Pad2)") (class "Default")
      (node (ref "C21") (pin "2") (pinfunction "2_2") (pintype "passive"))
      (node (ref "C25") (pin "2") (pinfunction "2_2") (pintype "passive"))
      (node (ref "R31") (pin "1") (pinfunction "1_1") (pintype "passive"))
      (node (ref "R36") (pin "2") (pinfunction "2_2") (pintype "passive"))
    )
    (net (code "40") (name "Net-(C22-Pad2)") (class "Default")
      (node (ref "C22") (pin "2") (pinfunction "2_2") (pintype "passive"))
      (node (ref "R38") (pin "2") (pinfunction "2_2") (pintype "passive"))
    )
    (net (code "41") (name "Net-(C23-Pad2)") (class "Default")
      (node (ref "C23") (pin "2") (pinfunction "2_2") (pintype "passive"))
      (node (ref "C24") (pin "1") (pinfunction "1_1") (pintype "passive"))
      (node (ref "J20") (pin "2") (pinfunction "2_2") (pintype "passive"))
      (node (ref "R39") (pin "2") (pinfunction "2_2") (pintype "passive"))
    )
    (net (code "42") (name "Net-(C24-Pad2)") (class "Default")
      (node (ref "C24") (pin "2") (pinfunction "2_2") (pintype "passive"))
      (node (ref "C32") (pin "2") (pinfunction "2_2") (pintype "passive"))
      (node (ref "J19") (pin "1") (pinfunction "1_1") (pintype "passive"))
    )
    (net (code "43") (name "Net-(C25-Pad1)") (class "Default")
      (node (ref "C25") (pin "1") (pinfunction "1_1") (pintype "passive"))
      (node (ref "C31") (pin "2") (pinfunction "2_2") (pintype "passive"))
      (node (ref "R46") (pin "1") (pinfunction "1_1") (pintype "passive"))
      (node (ref "R50") (pin "1") (pinfunction "1_1") (pintype "passive"))
    )
    (net (code "44") (name "Net-(C26-Pad1)") (class "Default")
      (node (ref "C26") (pin "1") (pinfunction "1_1") (pintype "passive"))
      (node (ref "J20") (pin "1") (pinfunction "1_1") (pintype "passive"))
    )
    (net (code "45") (name "Net-(C28-P)") (class "Default")
      (node (ref "C28") (pin "1") (pinfunction "P_1") (pintype "passive"))
      (node (ref "D11") (pin "2") (pinfunction "C_2") (pintype "passive"))
      (node (ref "K2") (pin "1") (pinfunction "1_1") (pintype "passive"))
    )
    (net (code "46") (name "Net-(C29-Pad1)") (class "Default")
      (node (ref "C29") (pin "1") (pinfunction "1_1") (pintype "passive"))
      (node (ref "J22") (pin "1") (pinfunction "1_1") (pintype "passive"))
    )
    (net (code "47") (name "Net-(C30-Pad1)") (class "Default")
      (node (ref "C30") (pin "1") (pinfunction "1_1") (pintype "passive"))
      (node (ref "C34") (pin "2") (pinfunction "2_2") (pintype "passive"))
      (node (ref "R39") (pin "1") (pinfunction "1_1") (pintype "passive"))
    )
    (net (code "48") (name "Net-(C30-Pad2)") (class "Default")
      (node (ref "C30") (pin "2") (pinfunction "2_2") (pintype "passive"))
      (node (ref "R47") (pin "1") (pinfunction "1_1") (pintype "passive"))
    )
    (net (code "49") (name "Net-(C32-Pad1)") (class "Default")
      (node (ref "C32") (pin "1") (pinfunction "1_1") (pintype "passive"))
      (node (ref "J25") (pin "1") (pinfunction "1_1") (pintype "passive"))
    )
    (net (code "50") (name "Net-(C33-Pad2)") (class "Default")
      (node (ref "C33") (pin "2") (pinfunction "2_2") (pintype "passive"))
      (node (ref "J19") (pin "3") (pinfunction "3_3") (pintype "passive"))
      (node (ref "R47") (pin "2") (pinfunction "2_2") (pintype "passive"))
      (node (ref "R51") (pin "2") (pinfunction "2_2") (pintype "passive"))
    )
    (net (code "51") (name "Net-(C34-Pad1)") (class "Default")
      (node (ref "C34") (pin "1") (pinfunction "1_1") (pintype "passive"))
      (node (ref "J25") (pin "2") (pinfunction "2_2") (pintype "passive"))
    )
    (net (code "52") (name "Net-(C35-Pad1)") (class "Default")
      (node (ref "C35") (pin "1") (pinfunction "1_1") (pintype "passive"))
      (node (ref "C36") (pin "1") (pinfunction "1_1") (pintype "passive"))
      (node (ref "R43") (pin "1") (pinfunction "1_1") (pintype "passive"))
      (node (ref "R55") (pin "1") (pinfunction "1_1") (pintype "passive"))
      (node (ref "R57") (pin "1") (pinfunction "1_1") (pintype "passive"))
    )
    (net (code "53") (name "Net-(C36-Pad2)") (class "Default")
      (node (ref "C36") (pin "2") (pinfunction "2_2") (pintype "passive"))
      (node (ref "J27") (pin "1") (pinfunction "1_1") (pintype "passive"))
    )
    (net (code "54") (name "Net-(D1-C)") (class "Default")
      (node (ref "D1") (pin "2") (pinfunction "C_2") (pintype "passive"))
      (node (ref "D2") (pin "1") (pinfunction "A_1") (pintype "passive"))
      (node (ref "D3") (pin "1") (pinfunction "A_1") (pintype "passive"))
      (node (ref "D4") (pin "2") (pinfunction "C_2") (pintype "passive"))
    )
    (net (code "55") (name "Net-(D3-C)") (class "Default")
      (node (ref "D3") (pin "2") (pinfunction "C_2") (pintype "passive"))
      (node (ref "D5") (pin "1") (pinfunction "A_1") (pintype "passive"))
    )
    (net (code "56") (name "Net-(D6-A)") (class "Default")
      (node (ref "C16") (pin "2") (pinfunction "2_2") (pintype "passive"))
      (node (ref "D6") (pin "1") (pinfunction "A_1") (pintype "passive"))
      (node (ref "D7") (pin "2") (pinfunction "C_2") (pintype "passive"))
      (node (ref "J12") (pin "2") (pinfunction "2_2") (pintype "passive"))
      (node (ref "R16") (pin "1") (pinfunction "1_1") (pintype "passive"))
    )
    (net (code "57") (name "Net-(J3-Pad2)") (class "Default")
      (node (ref "J3") (pin "2") (pinfunction "2_2") (pintype "passive"))
      (node (ref "R13") (pin "2") (pinfunction "2_2") (pintype "passive"))
    )
    (net (code "58") (name "Net-(J5-Pad2)") (class "Default")
      (node (ref "J5") (pin "2") (pinfunction "2_2") (pintype "passive"))
      (node (ref "R11") (pin "1") (pinfunction "1_1") (pintype "passive"))
    )
    (net (code "59") (name "Net-(J6-Pad2)") (class "Default")
      (node (ref "J6") (pin "2") (pinfunction "2_2") (pintype "passive"))
      (node (ref "R21") (pin "2") (pinfunction "2_2") (pintype "passive"))
    )
    (net (code "60") (name "Net-(J7-Pad2)") (class "Default")
      (node (ref "J7") (pin "2") (pinfunction "2_2") (pintype "passive"))
      (node (ref "R26") (pin "2") (pinfunction "2_2") (pintype "passive"))
    )
    (net (code "61") (name "Net-(J14-Pad2)") (class "Default")
      (node (ref "J14") (pin "2") (pinfunction "2_2") (pintype "passive"))
      (node (ref "R33") (pin "1") (pinfunction "1_1") (pintype "passive"))
    )
    (net (code "62") (name "Net-(J18-Pad2)") (class "Default")
      (node (ref "J18") (pin "2") (pinfunction "2_2") (pintype "passive"))
      (node (ref "R55") (pin "2") (pinfunction "2_2") (pintype "passive"))
    )
    (net (code "63") (name "Net-(J20-Pad3)") (class "Default")
      (node (ref "J20") (pin "3") (pinfunction "3_3") (pintype "passive"))
      (node (ref "R53") (pin "2") (pinfunction "2_2") (pintype "passive"))
    )
    (net (code "64") (name "Net-(J21-Pad2)") (class "Default")
      (node (ref "J21") (pin "2") (pinfunction "2_2") (pintype "passive"))
      (node (ref "R38") (pin "1") (pinfunction "1_1") (pintype "passive"))
    )
    (net (code "65") (name "Net-(J23-Pad2)") (class "Default")
      (node (ref "J23") (pin "2") (pinfunction "2_2") (pintype "passive"))
      (node (ref "R48") (pin "2") (pinfunction "2_2") (pintype "passive"))
    )
    (net (code "66") (name "Net-(J26-Pad1)") (class "Default")
      (node (ref "J26") (pin "1") (pinfunction "1_1") (pintype "passive"))
      (node (ref "J26") (pin "2") (pinfunction "2_2") (pintype "passive"))
      (node (ref "R51") (pin "1") (pinfunction "1_1") (pintype "passive"))
    )
    (net (code "67") (name "Net-(J27-Pad2)") (class "Default")
      (node (ref "J27") (pin "2") (pinfunction "2_2") (pintype "passive"))
      (node (ref "R57") (pin "2") (pinfunction "2_2") (pintype "passive"))
    )
    (net (code "68") (name "Net-(J27-Pad3)") (class "Default")
      (node (ref "J27") (pin "3") (pinfunction "3_3") (pintype "passive"))
      (node (ref "R56") (pin "1") (pinfunction "1_1") (pintype "passive"))
    )
    (net (code "69") (name "Net-(P1-Pad1)") (class "Default")
      (node (ref "P1") (pin "1") (pinfunction "1_1") (pintype "passive"))
      (node (ref "R30") (pin "1") (pinfunction "1_1") (pintype "passive"))
    )
    (net (code "70") (name "Net-(P1-Pad2)") (class "Default")
      (node (ref "P1") (pin "2") (pinfunction "2_2") (pintype "passive"))
      (node (ref "R29") (pin "2") (pinfunction "2_2") (pintype "passive"))
    )
    (net (code "71") (name "Net-(P2-Pad1)") (class "Default")
      (node (ref "P2") (pin "1") (pinfunction "1_1") (pintype "passive"))
      (node (ref "R42") (pin "1") (pinfunction "1_1") (pintype "passive"))
    )
    (net (code "72") (name "Net-(P2-Pad2)") (class "Default")
      (node (ref "P2") (pin "2") (pinfunction "2_2") (pintype "passive"))
      (node (ref "R41") (pin "2") (pinfunction "2_2") (pintype "passive"))
    )
    (net (code "73") (name "Net-(R15-Pad1)") (class "Default")
      (node (ref "R15") (pin "1") (pinfunction "1_1") (pintype "passive"))
      (node (ref "R17") (pin "1") (pinfunction "1_1") (pintype "passive"))
    )
    (net (code "74") (name "Net-(R34-Pad1)") (class "Default")
      (node (ref "R34") (pin "1") (pinfunction "1_1") (pintype "passive"))
      (node (ref "R43") (pin "2") (pinfunction "2_2") (pintype "passive"))
      (node (ref "R44") (pin "1") (pinfunction "1_1") (pintype "passive"))
      (node (ref "R49") (pin "2") (pinfunction "2_2") (pintype "passive"))
    )
    (net (code "75") (name "Net-(V1A-A1)") (class "Default")
      (node (ref "C10") (pin "2") (pinfunction "2_2") (pintype "passive"))
      (node (ref "C2") (pin "1") (pinfunction "1_1") (pintype "passive"))
      (node (ref "R1") (pin "1") (pinfunction "1_1") (pintype "passive"))
      (node (ref "V1") (pin "6") (pinfunction "A1_6") (pintype "passive"))
    )
    (net (code "76") (name "Net-(V1A-G1)") (class "Default")
      (node (ref "R12") (pin "2") (pinfunction "2_2") (pintype "passive"))
      (node (ref "V1") (pin "7") (pinfunction "G1_7") (pintype "passive"))
    )
    (net (code "77") (name "Net-(V1B-A2)") (class "Default")
      (node (ref "C1") (pin "1") (pinfunction "1_1") (pintype "passive"))
      (node (ref "C4") (pin "1") (pinfunction "1_1") (pintype "passive"))
      (node (ref "R3") (pin "1") (pinfunction "1_1") (pintype "passive"))
      (node (ref "V1") (pin "1") (pinfunction "A2_1") (pintype "passive"))
    )
    (net (code "78") (name "Net-(V1B-G2)") (class "Default")
      (node (ref "R14") (pin "2") (pinfunction "2_2") (pintype "passive"))
      (node (ref "R22") (pin "2") (pinfunction "2_2") (pintype "passive"))
      (node (ref "V1") (pin "2") (pinfunction "G2_2") (pintype "passive"))
    )
    (net (code "79") (name "Net-(V2A-A1)") (class "Default")
      (node (ref "C5") (pin "1") (pinfunction "1_1") (pintype "passive"))
      (node (ref "R2") (pin "1") (pinfunction "1_1") (pintype "passive"))
      (node (ref "V2") (pin "6") (pinfunction "A1_6") (pintype "passive"))
    )
    (net (code "80") (name "Net-(V2A-G1)") (class "Default")
      (node (ref "R11") (pin "2") (pinfunction "2_2") (pintype "passive"))
      (node (ref "R15") (pin "2") (pinfunction "2_2") (pintype "passive"))
      (node (ref "R16") (pin "2") (pinfunction "2_2") (pintype "passive"))
      (node (ref "R9") (pin "2") (pinfunction "2_2") (pintype "passive"))
      (node (ref "V2") (pin "7") (pinfunction "G1_7") (pintype "passive"))
    )
    (net (code "81") (name "Net-(V2A-K1)") (class "Default")
      (node (ref "R23") (pin "2") (pinfunction "2_2") (pintype "passive"))
      (node (ref "V2") (pin "8") (pinfunction "K1_8") (pintype "passive"))
    )
    (net (code "82") (name "Net-(V2B-G2)") (class "Default")
      (node (ref "C29") (pin "2") (pinfunction "2_2") (pintype "passive"))
      (node (ref "R52") (pin "2") (pinfunction "2_2") (pintype "passive"))
      (node (ref "V2") (pin "2") (pinfunction "G2_2") (pintype "passive"))
    )
    (net (code "83") (name "Net-(V2B-K2)") (class "Default")
      (node (ref "R54") (pin "2") (pinfunction "2_2") (pintype "passive"))
      (node (ref "V2") (pin "3") (pinfunction "K2_3") (pintype "passive"))
    )
    (net (code "84") (name "Net-(V3A-A1)") (class "Default")
      (node (ref "C7") (pin "1") (pinfunction "1_1") (pintype "passive"))
      (node (ref "R4") (pin "2") (pinfunction "2_2") (pintype "passive"))
      (node (ref "V3") (pin "6") (pinfunction "A1_6") (pintype "passive"))
    )
    (net (code "85") (name "Net-(V3A-K1)") (class "Default")
      (node (ref "C18") (pin "2") (pinfunction "2_2") (pintype "passive"))
      (node (ref "R28") (pin "2") (pinfunction "2_2") (pintype "passive"))
      (node (ref "V3") (pin "8") (pinfunction "K1_8") (pintype "passive"))
    )
    (net (code "86") (name "Net-(V3B-A2)") (class "Default")
      (node (ref "C8") (pin "1") (pinfunction "1_1") (pintype "passive"))
      (node (ref "R6") (pin "1") (pinfunction "1_1") (pintype "passive"))
      (node (ref "V3") (pin "1") (pinfunction "A2_1") (pintype "passive"))
    )
    (net (code "87") (name "Net-(V3B-G2)") (class "Default")
      (node (ref "J7") (pin "1") (pinfunction "1_1") (pintype "passive"))
      (node (ref "V3") (pin "2") (pinfunction "G2_2") (pintype "passive"))
    )
    (net (code "88") (name "Net-(V4A-A)") (class "Default")
      (node (ref "J14") (pin "1") (pinfunction "1_1") (pintype "passive"))
      (node (ref "J17") (pin "1") (pinfunction "1_1") (pintype "passive"))
      (node (ref "V4") (pin "3") (pinfunction "A_3") (pintype "passive"))
    )
    (net (code "89") (name "Net-(V4A-G1)") (class "Default")
      (node (ref "R31") (pin "2") (pinfunction "2_2") (pintype "passive"))
      (node (ref "V4") (pin "5") (pinfunction "G1_5") (pintype "passive"))
    )
    (net (code "90") (name "Net-(V4A-G2)") (class "Default")
      (node (ref "R33") (pin "2") (pinfunction "2_2") (pintype "passive"))
      (node (ref "V4") (pin "4") (pinfunction "G2_4") (pintype "passive"))
    )
    (net (code "91") (name "Net-(V4A-K)") (class "Default")
      (node (ref "R37") (pin "2") (pinfunction "2_2") (pintype "passive"))
      (node (ref "V4") (pin "8") (pinfunction "K_8") (pintype "passive"))
    )
    (net (code "92") (name "Net-(V5A-A1)") (class "Default")
      (node (ref "C21") (pin "1") (pinfunction "1_1") (pintype "passive"))
      (node (ref "R35") (pin "2") (pinfunction "2_2") (pintype "passive"))
      (node (ref "V5") (pin "6") (pinfunction "A1_6") (pintype "passive"))
    )
    (net (code "93") (name "Net-(V5A-K1)") (class "Default")
      (node (ref "R44") (pin "2") (pinfunction "2_2") (pintype "passive"))
      (node (ref "V5") (pin "3") (pinfunction "K2_3") (pintype "passive"))
      (node (ref "V5") (pin "8") (pinfunction "K1_8") (pintype "passive"))
    )
    (net (code "94") (name "Net-(V5B-A2)") (class "Default")
      (node (ref "C31") (pin "1") (pinfunction "1_1") (pintype "passive"))
      (node (ref "R45") (pin "1") (pinfunction "1_1") (pintype "passive"))
      (node (ref "V5") (pin "1") (pinfunction "A2_1") (pintype "passive"))
    )
    (net (code "95") (name "Net-(V5B-G2)") (class "Default")
      (node (ref "C35") (pin "2") (pinfunction "2_2") (pintype "passive"))
      (node (ref "R49") (pin "1") (pinfunction "1_1") (pintype "passive"))
      (node (ref "V5") (pin "2") (pinfunction "G2_2") (pintype "passive"))
    )
    (net (code "96") (name "Net-(V6A-A)") (class "Default")
      (node (ref "J17") (pin "3") (pinfunction "3_3") (pintype "passive"))
      (node (ref "J23") (pin "1") (pinfunction "1_1") (pintype "passive"))
      (node (ref "V6") (pin "3") (pinfunction "A_3") (pintype "passive"))
    )
    (net (code "97") (name "Net-(V6A-G1)") (class "Default")
      (node (ref "R50") (pin "2") (pinfunction "2_2") (pintype "passive"))
      (node (ref "V6") (pin "5") (pinfunction "G1_5") (pintype "passive"))
    )
    (net (code "98") (name "Net-(V6A-G2)") (class "Default")
      (node (ref "R48") (pin "1") (pinfunction "1_1") (pintype "passive"))
      (node (ref "V6") (pin "4") (pinfunction "G2_4") (pintype "passive"))
    )
    (net (code "99") (name "Net-(V6A-K)") (class "Default")
      (node (ref "R40") (pin "1") (pinfunction "1_1") (pintype "passive"))
      (node (ref "V6") (pin "8") (pinfunction "K_8") (pintype "passive"))
    )
    (net (code "100") (name "PI_GND") (class "Default")
      (node (ref "J30") (pin "2") (pinfunction "2_2") (pintype "passive"))
      (node (ref "J31") (pin "2") (pinfunction "2_2") (pintype "passive"))
      (node (ref "R56") (pin "2") (pinfunction "2_2") (pintype "passive"))
    )
    (net (code "101") (name "PRE_GND") (class "Default")
      (node (ref "C13") (pin "1") (pinfunction "1_1") (pintype "passive"))
      (node (ref "C14") (pin "2") (pinfunction "N_2") (pintype "passive"))
      (node (ref "C15") (pin "2") (pinfunction "N_2") (pintype "passive"))
      (node (ref "C16") (pin "1") (pinfunction "1_1") (pintype "passive"))
      (node (ref "C17") (pin "2") (pinfunction "N_2") (pintype "passive"))
      (node (ref "C18") (pin "1") (pinfunction "1_1") (pintype "passive"))
      (node (ref "C33") (pin "1") (pinfunction "1_1") (pintype "passive"))
      (node (ref "D4") (pin "1") (pinfunction "A_1") (pintype "passive"))
      (node (ref "D5") (pin "2") (pinfunction "C_2") (pintype "passive"))
      (node (ref "D6") (pin "2") (pinfunction "C_2") (pintype "passive"))
      (node (ref "D7") (pin "1") (pinfunction "A_1") (pintype "passive"))
      (node (ref "J1") (pin "3") (pinfunction "3_3") (pintype "passive"))
      (node (ref "J10") (pin "3") (pinfunction "3_3") (pintype "passive"))
      (node (ref "J11") (pin "3") (pinfunction "3_3") (pintype "passive"))
      (node (ref "J2") (pin "1") (pinfunction "1_1") (pintype "passive"))
      (node (ref "J21") (pin "3") (pinfunction "3_3") (pintype "passive"))
      (node (ref "J22") (pin "3") (pinfunction "3_3") (pintype "passive"))
      (node (ref "J25") (pin "3") (pinfunction "3_3") (pintype "passive"))
      (node (ref "J26") (pin "3") (pinfunction "3_3") (pintype "passive"))
      (node (ref "J28") (pin "2") (pinfunction "2_2") (pintype "passive"))
      (node (ref "J29") (pin "2") (pinfunction "2_2") (pintype "passive"))
      (node (ref "J3") (pin "1") (pinfunction "1_1") (pintype "passive"))
      (node (ref "J4") (pin "3") (pinfunction "3_3") (pintype "passive"))
      (node (ref "J5") (pin "3") (pinfunction "3_3") (pintype "passive"))
      (node (ref "J8") (pin "2") (pinfunction "2_2") (pintype "passive"))
      (node (ref "K1") (pin "13") (pinfunction "13_13") (pintype "passive"))
      (node (ref "K2") (pin "6") (pinfunction "6_6") (pintype "passive"))
      (node (ref "R18") (pin "1") (pinfunction "1_1") (pintype "passive"))
      (node (ref "R19") (pin "1") (pinfunction "1_1") (pintype "passive"))
      (node (ref "R20") (pin "1") (pinfunction "1_1") (pintype "passive"))
      (node (ref "R21") (pin "1") (pinfunction "1_1") (pintype "passive"))
      (node (ref "R23") (pin "1") (pinfunction "1_1") (pintype "passive"))
      (node (ref "R24") (pin "1") (pinfunction "1_1") (pintype "passive"))
      (node (ref "R25") (pin "1") (pinfunction "1_1") (pintype "passive"))
      (node (ref "R26") (pin "1") (pinfunction "1_1") (pintype "passive"))
      (node (ref "R27") (pin "1") (pinfunction "1_1") (pintype "passive"))
      (node (ref "R28") (pin "1") (pinfunction "1_1") (pintype "passive"))
      (node (ref "R52") (pin "1") (pinfunction "1_1") (pintype "passive"))
      (node (ref "R53") (pin "1") (pinfunction "1_1") (pintype "passive"))
      (node (ref "R54") (pin "1") (pinfunction "1_1") (pintype "passive"))
    )
    (net (code "102") (name "PWR_GND") (class "Default")
      (node (ref "J18") (pin "1") (pinfunction "1_1") (pintype "passive"))
      (node (ref "J32") (pin "1") (pinfunction "1_1") (pintype "passive"))
      (node (ref "R37") (pin "1") (pinfunction "1_1") (pintype "passive"))
      (node (ref "R40") (pin "2") (pinfunction "2_2") (pintype "passive"))
      (node (ref "V4") (pin "1") (pinfunction "G3_1") (pintype "passive"))
      (node (ref "V6") (pin "1") (pinfunction "G3_1") (pintype "passive"))
    )
    (net (code "103") (name "unconnected-(K2-Pad8)") (class "Default")
      (node (ref "K2") (pin "8") (pinfunction "8_8") (pintype "passive"))
    )
    (net (code "104") (name "unconnected-(K2-Pad9)") (class "Default")
      (node (ref "K2") (pin "9") (pinfunction "9_9") (pintype "passive"))
    )
    (net (code "105") (name "unconnected-(K2-Pad11)") (class "Default")
      (node (ref "K2") (pin "11") (pinfunction "11_11") (pintype "passive"))
    )
    (net (code "106") (name "unconnected-(K2-Pad13)") (class "Default")
      (node (ref "K2") (pin "13") (pinfunction "13_13") (pintype "passive"))
    )
  )
)
